# H16R6.net
KiCad netlist of a schematic drawn in EAGLE
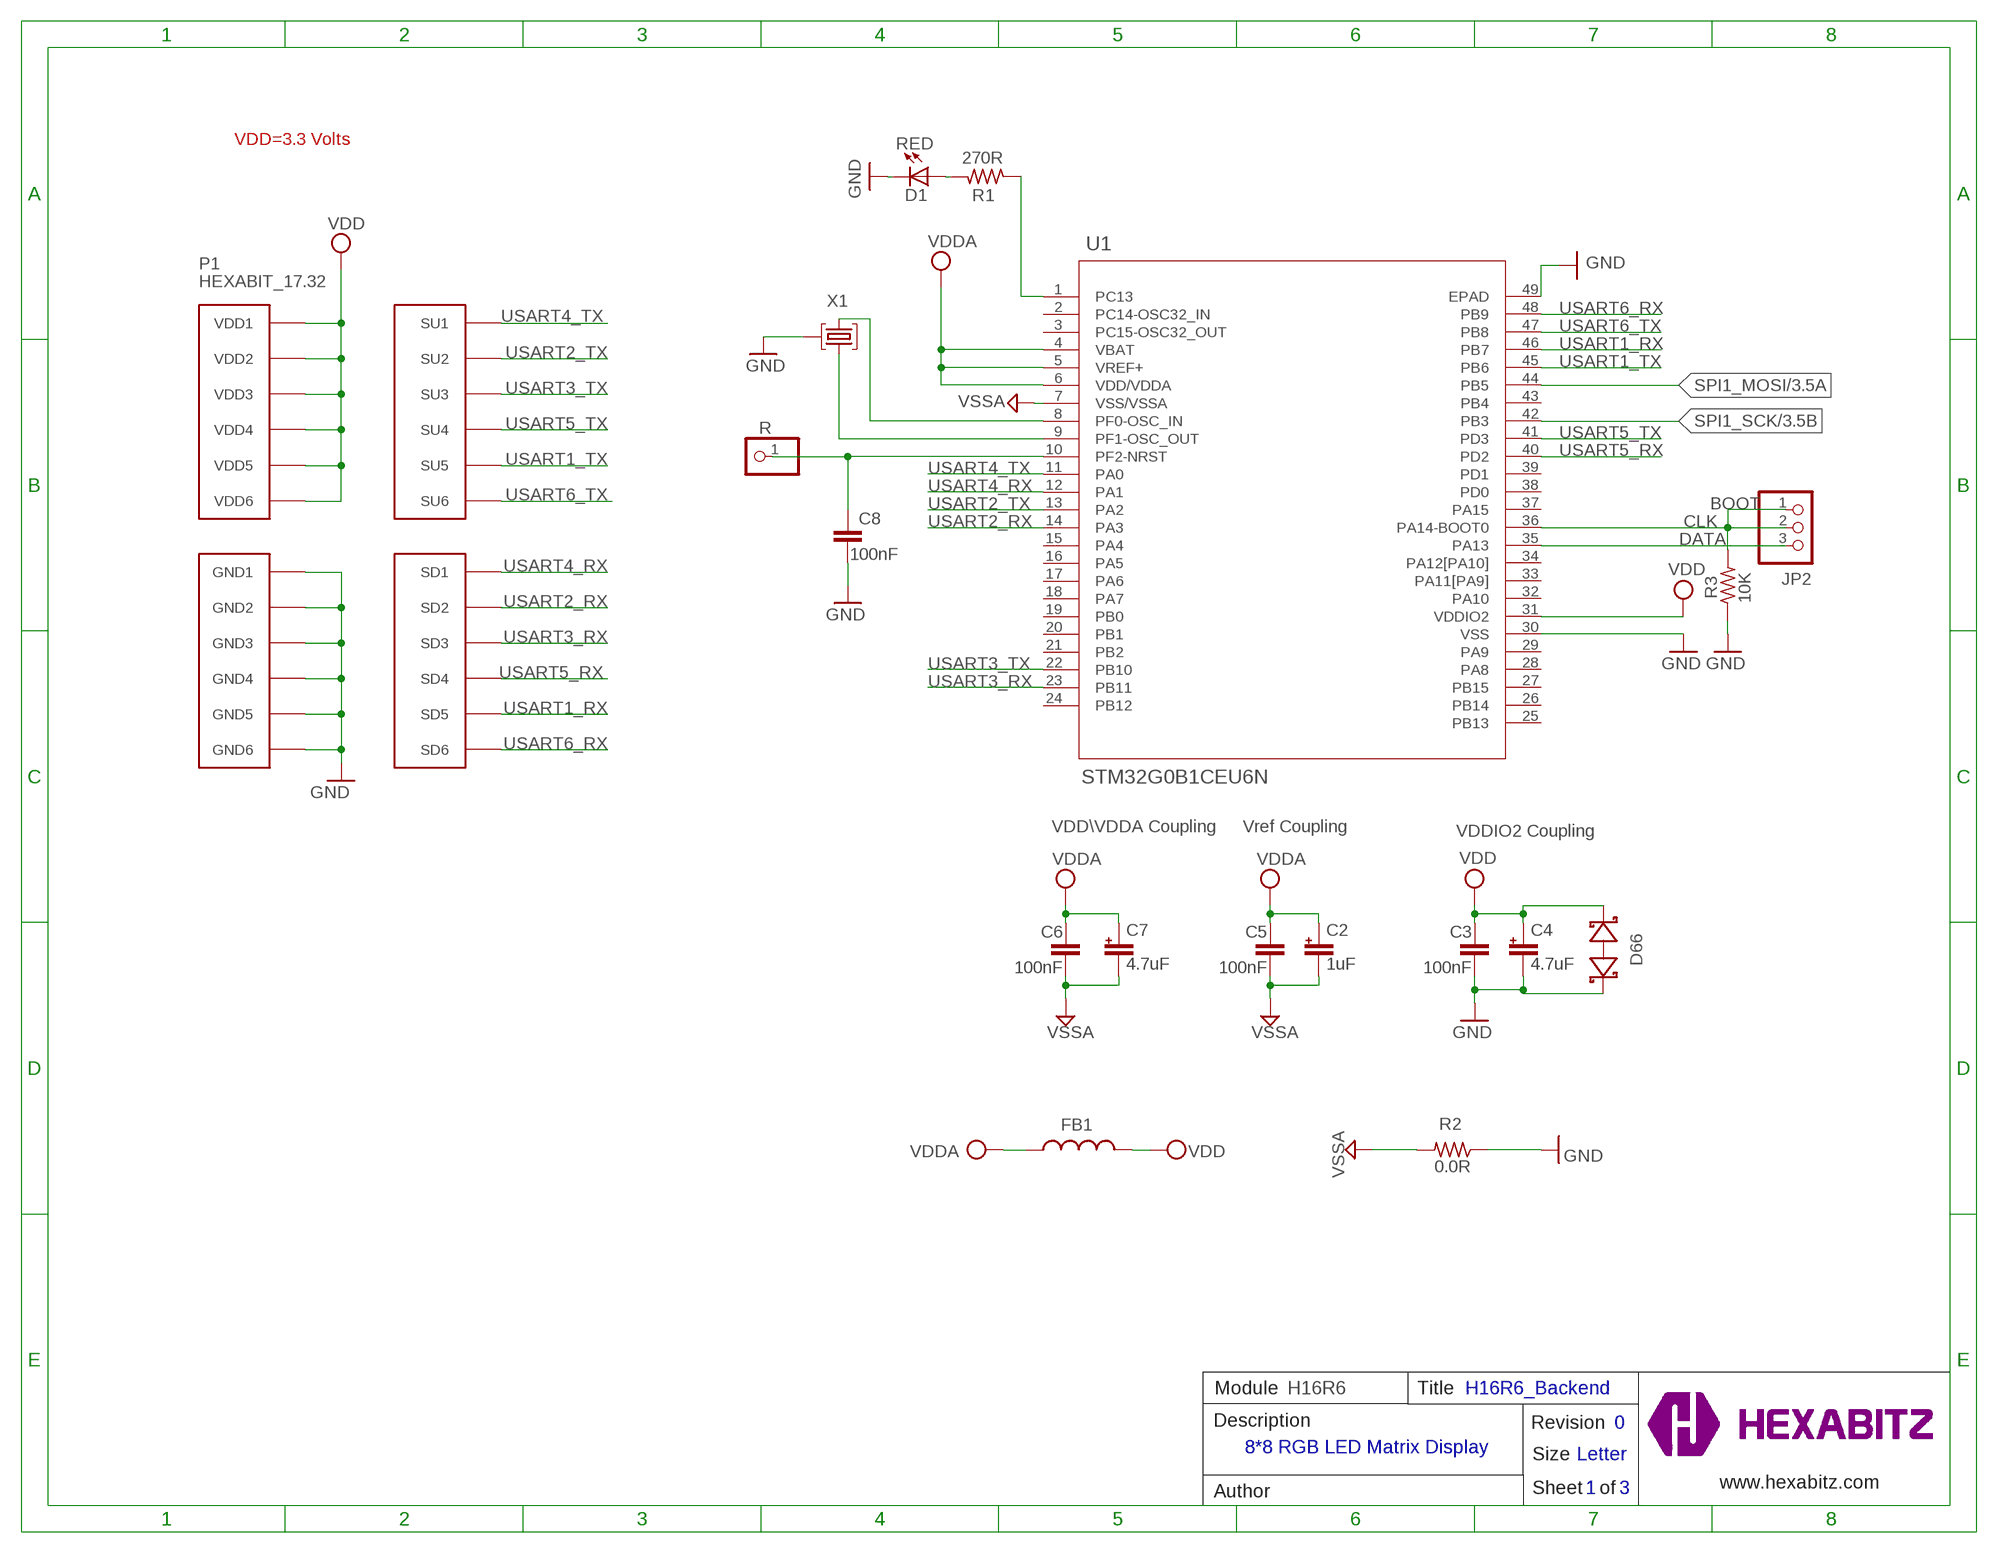
[diagram p0: schematic, sheet 1]
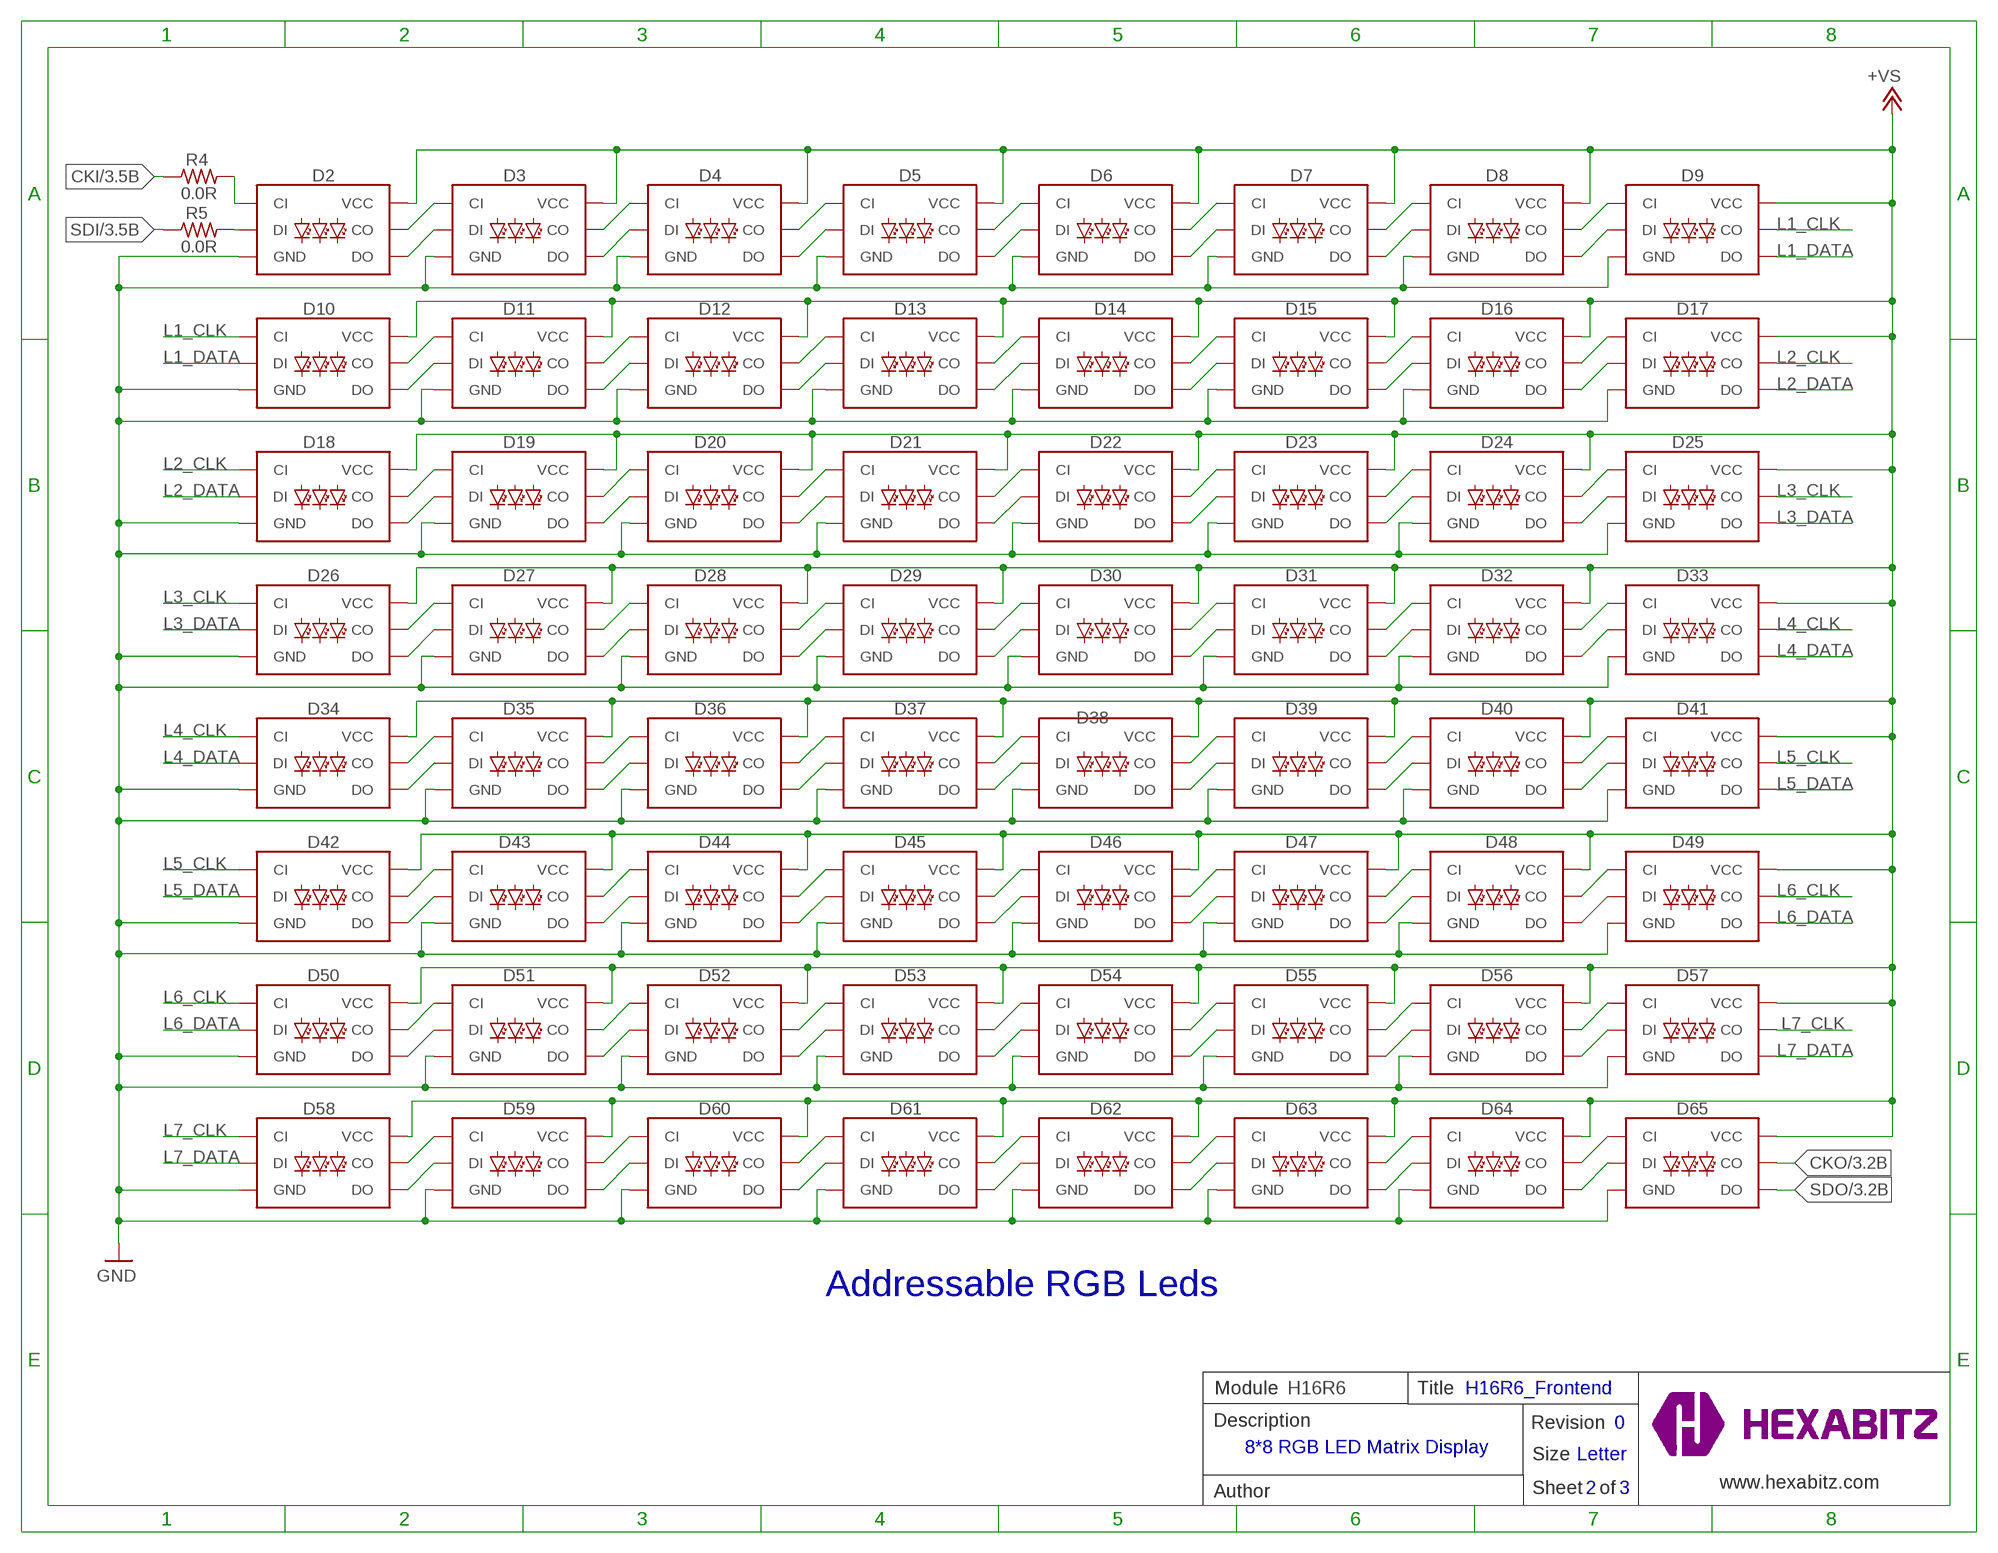
[diagram p1: schematic, sheet 2]
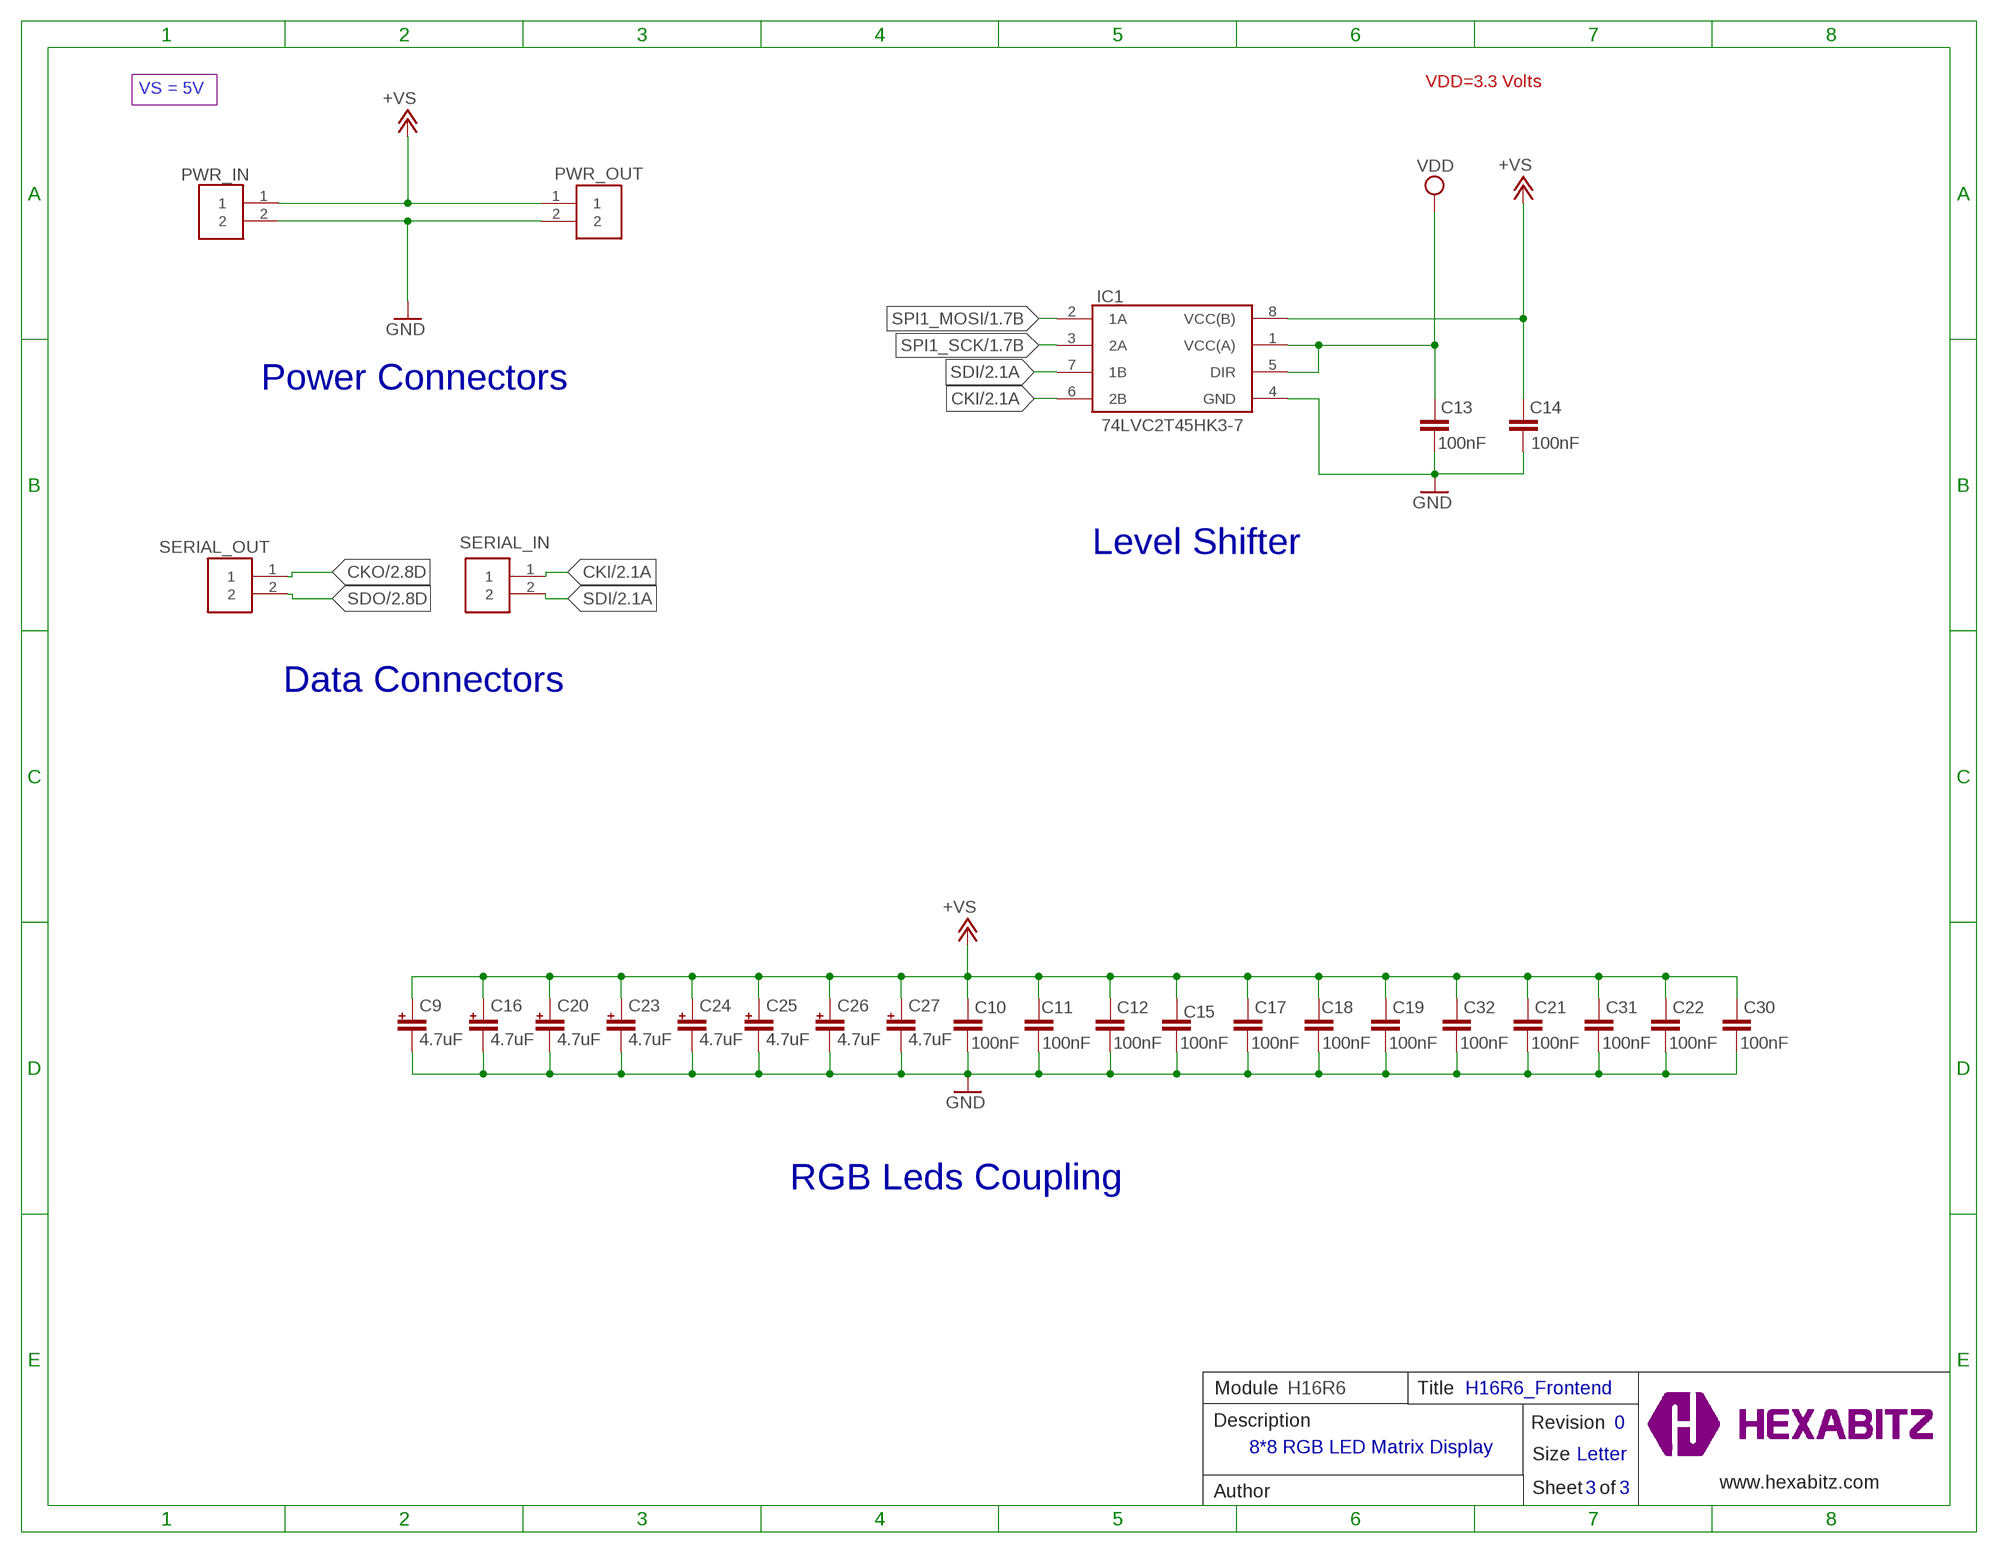
[diagram p2: schematic, sheet 3]

(export (version "E")
  (design (tool "Eeschema 10.0.6"))
  (components
    (comp (ref "C2")
      (value "1uF")
      (footprint "eagle-import:C-0402-POL")
      (libsource (lib "eagle-import") (part "C-0402-POL"))
    )
    (comp (ref "C3")
      (value "100nF")
      (footprint "eagle-import:C-0402")
      (libsource (lib "eagle-import") (part "C-0402"))
    )
    (comp (ref "C4")
      (value "4.7uF")
      (footprint "eagle-import:C-0402-POL")
      (libsource (lib "eagle-import") (part "C-0402-POL"))
    )
    (comp (ref "C5")
      (value "100nF")
      (footprint "eagle-import:C-0402")
      (libsource (lib "eagle-import") (part "C-0402"))
    )
    (comp (ref "C6")
      (value "100nF")
      (footprint "eagle-import:C-0402")
      (libsource (lib "eagle-import") (part "C-0402"))
    )
    (comp (ref "C7")
      (value "4.7uF")
      (footprint "eagle-import:C-0402-POL")
      (libsource (lib "eagle-import") (part "C-0402-POL"))
    )
    (comp (ref "C8")
      (value "100nF")
      (footprint "eagle-import:C-0402")
      (libsource (lib "eagle-import") (part "C-0402"))
    )
    (comp (ref "D1")
      (value "RED")
      (footprint "eagle-import:VLMS1300-GS08")
      (fields
        (field (name "MPN") "VLMS1300-GS08")
        (field (name "MFN") "Vishay")
        (field (name "MPN_1") "VLMS1300-GS08")
        (field (name "OCTOPART_URL") "https://octopart.com/vlms1300-gs08-vishay-21709201?r=sp&s=_gcP4_q8T1SC6PJQPTQ9yA")
      )
      (libsource (lib "eagle-import") (part "VLMS1300-GS08"))
    )
    (comp (ref "D66")
      (value "BOURNS_CDSOD323-T03SCBOURNS_CDSOD323-T03SC_0_0")
      (footprint "eagle-import:BOURNS_CDSOD323-T03SC_0")
      (fields (field (name "MPN") "CDSOD323-T03SC"))
      (libsource (lib "eagle-import") (part "BOURNS_CDSOD323-T03SCBOURNS_CDSOD323-T03SC_0_0"))
    )
    (comp (ref "FB1")
      (value "FB-TDK_MMZ1608Y300B")
      (footprint "eagle-import:FB-TDK_MMZ1608Y300B")
      (fields
        (field (name "MFN") "TDK ")
        (field (name "MPN") "MMZ1608Y300B")
        (field (name "OCTOPART_URL") "https://octopart.com/mmz1608y300b-tdk-368280?r=sp&s=cd9_2ZEqQ9q9UNBuQgHAiA")
      )
      (libsource (lib "eagle-import") (part "FB-TDK_MMZ1608Y300B"))
    )
    (comp (ref "JP2")
      (value "PINHD-1X3")
      (footprint "eagle-import:1X03")
      (libsource (lib "eagle-import") (part "PINHD-1X3"))
    )
    (comp (ref "P1")
      (value "HEXABIT_17.32")
      (footprint "eagle-import:HEXABIT_17.32")
      (libsource (lib "eagle-import") (part "HEXABIT_?17.32"))
    )
    (comp (ref "R")
      (value "R")
      (footprint "eagle-import:1X01")
      (fields (field (name "MPN") "87227-1"))
      (libsource (lib "eagle-import") (part "PINHD-1X1"))
    )
    (comp (ref "R1")
      (value "270R")
      (footprint "eagle-import:R-0402")
      (libsource (lib "eagle-import") (part "R-0402"))
    )
    (comp (ref "R2")
      (value "0.0R")
      (footprint "eagle-import:R-0402")
      (fields
        (field (name "MFN") "Yageo")
        (field (name "MPN") "RC0603JR-070RL")
        (field (name "OCTOPART_URL") "https://octopart.com/rc0603jr-070rl-yageo-1241539?r=sp&s=X2NteqRjRNWrnx42Y0aliA")
        (field (name "RESISTANCE") "0.0 Ohm")
      )
      (libsource (lib "eagle-import") (part "R-0402"))
    )
    (comp (ref "R3")
      (value "10K")
      (footprint "eagle-import:R-0402")
      (libsource (lib "eagle-import") (part "R-0402"))
    )
    (comp (ref "TRIMBLE-LOGO1")
      (value "HEXA-LOGO")
      (footprint "eagle-import:HEXA-LOGO")
      (libsource (lib "eagle-import") (part "HEXA-LOGO"))
    )
    (comp (ref "U1")
      (value "STM32G0B1CEU6N")
      (footprint "eagle-import:HEXABITZ_ICS_QFN_B1CEU6_STM-L")
      (libsource (lib "eagle-import") (part "STM32G0B1CEU6N"))
    )
    (comp (ref "X1")
      (value "XTALL_CSTCE8M00G52")
      (footprint "eagle-import:XTALL_CSTCE8M00G52")
      (fields (field (name "MPN") "CSTCE8M00G52Z-R0"))
      (libsource (lib "eagle-import") (part "XTALL_CSTCE8M00G52"))
    )
    (comp (ref "C9")
      (value "4.7uF")
      (footprint "eagle-import:C-0402-POL")
      (libsource (lib "eagle-import") (part "C-0402-POL"))
    )
    (comp (ref "C10")
      (value "100nF")
      (footprint "eagle-import:C-0402")
      (libsource (lib "eagle-import") (part "C-0402"))
    )
    (comp (ref "C11")
      (value "100nF")
      (footprint "eagle-import:C-0402")
      (libsource (lib "eagle-import") (part "C-0402"))
    )
    (comp (ref "C12")
      (value "100nF")
      (footprint "eagle-import:C-0402")
      (libsource (lib "eagle-import") (part "C-0402"))
    )
    (comp (ref "C13")
      (value "100nF")
      (footprint "eagle-import:C-0402")
      (libsource (lib "eagle-import") (part "C-0402"))
    )
    (comp (ref "C14")
      (value "100nF")
      (footprint "eagle-import:C-0402")
      (libsource (lib "eagle-import") (part "C-0402"))
    )
    (comp (ref "C15")
      (value "100nF")
      (footprint "eagle-import:C-0402")
      (libsource (lib "eagle-import") (part "C-0402"))
    )
    (comp (ref "C16")
      (value "4.7uF")
      (footprint "eagle-import:C-0402-POL")
      (libsource (lib "eagle-import") (part "C-0402-POL"))
    )
    (comp (ref "C17")
      (value "100nF")
      (footprint "eagle-import:C-0402")
      (libsource (lib "eagle-import") (part "C-0402"))
    )
    (comp (ref "C18")
      (value "100nF")
      (footprint "eagle-import:C-0402")
      (libsource (lib "eagle-import") (part "C-0402"))
    )
    (comp (ref "C19")
      (value "100nF")
      (footprint "eagle-import:C-0402")
      (libsource (lib "eagle-import") (part "C-0402"))
    )
    (comp (ref "C20")
      (value "4.7uF")
      (footprint "eagle-import:C-0402-POL")
      (libsource (lib "eagle-import") (part "C-0402-POL"))
    )
    (comp (ref "C21")
      (value "100nF")
      (footprint "eagle-import:C-0402")
      (libsource (lib "eagle-import") (part "C-0402"))
    )
    (comp (ref "C22")
      (value "100nF")
      (footprint "eagle-import:C-0402")
      (libsource (lib "eagle-import") (part "C-0402"))
    )
    (comp (ref "C23")
      (value "4.7uF")
      (footprint "eagle-import:C-0402-POL")
      (libsource (lib "eagle-import") (part "C-0402-POL"))
    )
    (comp (ref "C24")
      (value "4.7uF")
      (footprint "eagle-import:C-0402-POL")
      (libsource (lib "eagle-import") (part "C-0402-POL"))
    )
    (comp (ref "C25")
      (value "4.7uF")
      (footprint "eagle-import:C-0402-POL")
      (libsource (lib "eagle-import") (part "C-0402-POL"))
    )
    (comp (ref "C26")
      (value "4.7uF")
      (footprint "eagle-import:C-0402-POL")
      (libsource (lib "eagle-import") (part "C-0402-POL"))
    )
    (comp (ref "C27")
      (value "4.7uF")
      (footprint "eagle-import:C-0402-POL")
      (libsource (lib "eagle-import") (part "C-0402-POL"))
    )
    (comp (ref "C30")
      (value "100nF")
      (footprint "eagle-import:C-0402")
      (libsource (lib "eagle-import") (part "C-0402"))
    )
    (comp (ref "C31")
      (value "100nF")
      (footprint "eagle-import:C-0402")
      (libsource (lib "eagle-import") (part "C-0402"))
    )
    (comp (ref "C32")
      (value "100nF")
      (footprint "eagle-import:C-0402")
      (libsource (lib "eagle-import") (part "C-0402"))
    )
    (comp (ref "IC1")
      (value "74LVC2T45HK3-7")
      (footprint "eagle-import:74LVC2T45HK37")
      (fields (field (name "MOUSER_PART_NUMBER") "621-74LVC2T45HK3-7"))
      (libsource (lib "eagle-import") (part "74LVC2T45HK3-7"))
    )
    (comp (ref "PWR_IN")
      (value "3-644456-2")
      (footprint "eagle-import:TE_3-644456-2")
      (fields (field (name "MF") "TE Connectivity") (field (name "MPN") "87224-1"))
      (libsource (lib "eagle-import") (part "3-644456-2"))
    )
    (comp (ref "PWR_OUT")
      (value "3-644456-2")
      (footprint "eagle-import:TE_3-644456-2")
      (fields (field (name "MF") "TE Connectivity") (field (name "MPN") "87224-1"))
      (libsource (lib "eagle-import") (part "3-644456-2"))
    )
    (comp (ref "SERIAL_IN")
      (value "3-644456-2")
      (footprint "eagle-import:TE_3-644456-2")
      (fields (field (name "MF") "TE Connectivity") (field (name "MPN") "87224-1"))
      (libsource (lib "eagle-import") (part "3-644456-2"))
    )
    (comp (ref "SERIAL_OUT")
      (value "3-644456-2")
      (footprint "eagle-import:TE_3-644456-2")
      (fields (field (name "MF") "TE Connectivity") (field (name "MPN") "87224-1"))
      (libsource (lib "eagle-import") (part "3-644456-2"))
    )
    (comp (ref "D2")
      (value "SPARKFUN-LED_APA102-2020")
      (footprint "eagle-import:SPARKFUN-LED_APA102-2020")
      (libsource (lib "eagle-import") (part "SPARKFUN-LED_APA102-2020"))
    )
    (comp (ref "D3")
      (value "SPARKFUN-LED_APA102-2020")
      (footprint "eagle-import:SPARKFUN-LED_APA102-2020")
      (libsource (lib "eagle-import") (part "SPARKFUN-LED_APA102-2020"))
    )
    (comp (ref "D4")
      (value "SPARKFUN-LED_APA102-2020")
      (footprint "eagle-import:SPARKFUN-LED_APA102-2020")
      (libsource (lib "eagle-import") (part "SPARKFUN-LED_APA102-2020"))
    )
    (comp (ref "D5")
      (value "SPARKFUN-LED_APA102-2020")
      (footprint "eagle-import:SPARKFUN-LED_APA102-2020")
      (libsource (lib "eagle-import") (part "SPARKFUN-LED_APA102-2020"))
    )
    (comp (ref "D6")
      (value "SPARKFUN-LED_APA102-2020")
      (footprint "eagle-import:SPARKFUN-LED_APA102-2020")
      (libsource (lib "eagle-import") (part "SPARKFUN-LED_APA102-2020"))
    )
    (comp (ref "D7")
      (value "SPARKFUN-LED_APA102-2020")
      (footprint "eagle-import:SPARKFUN-LED_APA102-2020")
      (libsource (lib "eagle-import") (part "SPARKFUN-LED_APA102-2020"))
    )
    (comp (ref "D8")
      (value "SPARKFUN-LED_APA102-2020")
      (footprint "eagle-import:SPARKFUN-LED_APA102-2020")
      (libsource (lib "eagle-import") (part "SPARKFUN-LED_APA102-2020"))
    )
    (comp (ref "D9")
      (value "SPARKFUN-LED_APA102-2020")
      (footprint "eagle-import:SPARKFUN-LED_APA102-2020")
      (libsource (lib "eagle-import") (part "SPARKFUN-LED_APA102-2020"))
    )
    (comp (ref "D10")
      (value "SPARKFUN-LED_APA102-2020")
      (footprint "eagle-import:SPARKFUN-LED_APA102-2020")
      (libsource (lib "eagle-import") (part "SPARKFUN-LED_APA102-2020"))
    )
    (comp (ref "D11")
      (value "SPARKFUN-LED_APA102-2020")
      (footprint "eagle-import:SPARKFUN-LED_APA102-2020")
      (libsource (lib "eagle-import") (part "SPARKFUN-LED_APA102-2020"))
    )
    (comp (ref "D12")
      (value "SPARKFUN-LED_APA102-2020")
      (footprint "eagle-import:SPARKFUN-LED_APA102-2020")
      (libsource (lib "eagle-import") (part "SPARKFUN-LED_APA102-2020"))
    )
    (comp (ref "D13")
      (value "SPARKFUN-LED_APA102-2020")
      (footprint "eagle-import:SPARKFUN-LED_APA102-2020")
      (libsource (lib "eagle-import") (part "SPARKFUN-LED_APA102-2020"))
    )
    (comp (ref "D14")
      (value "SPARKFUN-LED_APA102-2020")
      (footprint "eagle-import:SPARKFUN-LED_APA102-2020")
      (libsource (lib "eagle-import") (part "SPARKFUN-LED_APA102-2020"))
    )
    (comp (ref "D15")
      (value "SPARKFUN-LED_APA102-2020")
      (footprint "eagle-import:SPARKFUN-LED_APA102-2020")
      (libsource (lib "eagle-import") (part "SPARKFUN-LED_APA102-2020"))
    )
    (comp (ref "D16")
      (value "SPARKFUN-LED_APA102-2020")
      (footprint "eagle-import:SPARKFUN-LED_APA102-2020")
      (libsource (lib "eagle-import") (part "SPARKFUN-LED_APA102-2020"))
    )
    (comp (ref "D17")
      (value "SPARKFUN-LED_APA102-2020")
      (footprint "eagle-import:SPARKFUN-LED_APA102-2020")
      (libsource (lib "eagle-import") (part "SPARKFUN-LED_APA102-2020"))
    )
    (comp (ref "D18")
      (value "SPARKFUN-LED_APA102-2020")
      (footprint "eagle-import:SPARKFUN-LED_APA102-2020")
      (libsource (lib "eagle-import") (part "SPARKFUN-LED_APA102-2020"))
    )
    (comp (ref "D19")
      (value "SPARKFUN-LED_APA102-2020")
      (footprint "eagle-import:SPARKFUN-LED_APA102-2020")
      (libsource (lib "eagle-import") (part "SPARKFUN-LED_APA102-2020"))
    )
    (comp (ref "D20")
      (value "SPARKFUN-LED_APA102-2020")
      (footprint "eagle-import:SPARKFUN-LED_APA102-2020")
      (libsource (lib "eagle-import") (part "SPARKFUN-LED_APA102-2020"))
    )
    (comp (ref "D21")
      (value "SPARKFUN-LED_APA102-2020")
      (footprint "eagle-import:SPARKFUN-LED_APA102-2020")
      (libsource (lib "eagle-import") (part "SPARKFUN-LED_APA102-2020"))
    )
    (comp (ref "D22")
      (value "SPARKFUN-LED_APA102-2020")
      (footprint "eagle-import:SPARKFUN-LED_APA102-2020")
      (libsource (lib "eagle-import") (part "SPARKFUN-LED_APA102-2020"))
    )
    (comp (ref "D23")
      (value "SPARKFUN-LED_APA102-2020")
      (footprint "eagle-import:SPARKFUN-LED_APA102-2020")
      (libsource (lib "eagle-import") (part "SPARKFUN-LED_APA102-2020"))
    )
    (comp (ref "D24")
      (value "SPARKFUN-LED_APA102-2020")
      (footprint "eagle-import:SPARKFUN-LED_APA102-2020")
      (libsource (lib "eagle-import") (part "SPARKFUN-LED_APA102-2020"))
    )
    (comp (ref "D25")
      (value "SPARKFUN-LED_APA102-2020")
      (footprint "eagle-import:SPARKFUN-LED_APA102-2020")
      (libsource (lib "eagle-import") (part "SPARKFUN-LED_APA102-2020"))
    )
    (comp (ref "D26")
      (value "SPARKFUN-LED_APA102-2020")
      (footprint "eagle-import:SPARKFUN-LED_APA102-2020")
      (libsource (lib "eagle-import") (part "SPARKFUN-LED_APA102-2020"))
    )
    (comp (ref "D27")
      (value "SPARKFUN-LED_APA102-2020")
      (footprint "eagle-import:SPARKFUN-LED_APA102-2020")
      (libsource (lib "eagle-import") (part "SPARKFUN-LED_APA102-2020"))
    )
    (comp (ref "D28")
      (value "SPARKFUN-LED_APA102-2020")
      (footprint "eagle-import:SPARKFUN-LED_APA102-2020")
      (libsource (lib "eagle-import") (part "SPARKFUN-LED_APA102-2020"))
    )
    (comp (ref "D29")
      (value "SPARKFUN-LED_APA102-2020")
      (footprint "eagle-import:SPARKFUN-LED_APA102-2020")
      (libsource (lib "eagle-import") (part "SPARKFUN-LED_APA102-2020"))
    )
    (comp (ref "D30")
      (value "SPARKFUN-LED_APA102-2020")
      (footprint "eagle-import:SPARKFUN-LED_APA102-2020")
      (libsource (lib "eagle-import") (part "SPARKFUN-LED_APA102-2020"))
    )
    (comp (ref "D31")
      (value "SPARKFUN-LED_APA102-2020")
      (footprint "eagle-import:SPARKFUN-LED_APA102-2020")
      (libsource (lib "eagle-import") (part "SPARKFUN-LED_APA102-2020"))
    )
    (comp (ref "D32")
      (value "SPARKFUN-LED_APA102-2020")
      (footprint "eagle-import:SPARKFUN-LED_APA102-2020")
      (libsource (lib "eagle-import") (part "SPARKFUN-LED_APA102-2020"))
    )
    (comp (ref "D33")
      (value "SPARKFUN-LED_APA102-2020")
      (footprint "eagle-import:SPARKFUN-LED_APA102-2020")
      (libsource (lib "eagle-import") (part "SPARKFUN-LED_APA102-2020"))
    )
    (comp (ref "D34")
      (value "SPARKFUN-LED_APA102-2020")
      (footprint "eagle-import:SPARKFUN-LED_APA102-2020")
      (libsource (lib "eagle-import") (part "SPARKFUN-LED_APA102-2020"))
    )
    (comp (ref "D35")
      (value "SPARKFUN-LED_APA102-2020")
      (footprint "eagle-import:SPARKFUN-LED_APA102-2020")
      (libsource (lib "eagle-import") (part "SPARKFUN-LED_APA102-2020"))
    )
    (comp (ref "D36")
      (value "SPARKFUN-LED_APA102-2020")
      (footprint "eagle-import:SPARKFUN-LED_APA102-2020")
      (libsource (lib "eagle-import") (part "SPARKFUN-LED_APA102-2020"))
    )
    (comp (ref "D37")
      (value "SPARKFUN-LED_APA102-2020")
      (footprint "eagle-import:SPARKFUN-LED_APA102-2020")
      (libsource (lib "eagle-import") (part "SPARKFUN-LED_APA102-2020"))
    )
    (comp (ref "D38")
      (value "SPARKFUN-LED_APA102-2020")
      (footprint "eagle-import:SPARKFUN-LED_APA102-2020")
      (libsource (lib "eagle-import") (part "SPARKFUN-LED_APA102-2020"))
    )
    (comp (ref "D39")
      (value "SPARKFUN-LED_APA102-2020")
      (footprint "eagle-import:SPARKFUN-LED_APA102-2020")
      (libsource (lib "eagle-import") (part "SPARKFUN-LED_APA102-2020"))
    )
    (comp (ref "D40")
      (value "SPARKFUN-LED_APA102-2020")
      (footprint "eagle-import:SPARKFUN-LED_APA102-2020")
      (libsource (lib "eagle-import") (part "SPARKFUN-LED_APA102-2020"))
    )
    (comp (ref "D41")
      (value "SPARKFUN-LED_APA102-2020")
      (footprint "eagle-import:SPARKFUN-LED_APA102-2020")
      (libsource (lib "eagle-import") (part "SPARKFUN-LED_APA102-2020"))
    )
    (comp (ref "D42")
      (value "SPARKFUN-LED_APA102-2020")
      (footprint "eagle-import:SPARKFUN-LED_APA102-2020")
      (libsource (lib "eagle-import") (part "SPARKFUN-LED_APA102-2020"))
    )
    (comp (ref "D43")
      (value "SPARKFUN-LED_APA102-2020")
      (footprint "eagle-import:SPARKFUN-LED_APA102-2020")
      (libsource (lib "eagle-import") (part "SPARKFUN-LED_APA102-2020"))
    )
    (comp (ref "D44")
      (value "SPARKFUN-LED_APA102-2020")
      (footprint "eagle-import:SPARKFUN-LED_APA102-2020")
      (libsource (lib "eagle-import") (part "SPARKFUN-LED_APA102-2020"))
    )
    (comp (ref "D45")
      (value "SPARKFUN-LED_APA102-2020")
      (footprint "eagle-import:SPARKFUN-LED_APA102-2020")
      (libsource (lib "eagle-import") (part "SPARKFUN-LED_APA102-2020"))
    )
    (comp (ref "D46")
      (value "SPARKFUN-LED_APA102-2020")
      (footprint "eagle-import:SPARKFUN-LED_APA102-2020")
      (libsource (lib "eagle-import") (part "SPARKFUN-LED_APA102-2020"))
    )
    (comp (ref "D47")
      (value "SPARKFUN-LED_APA102-2020")
      (footprint "eagle-import:SPARKFUN-LED_APA102-2020")
      (libsource (lib "eagle-import") (part "SPARKFUN-LED_APA102-2020"))
    )
    (comp (ref "D48")
      (value "SPARKFUN-LED_APA102-2020")
      (footprint "eagle-import:SPARKFUN-LED_APA102-2020")
      (libsource (lib "eagle-import") (part "SPARKFUN-LED_APA102-2020"))
    )
    (comp (ref "D49")
      (value "SPARKFUN-LED_APA102-2020")
      (footprint "eagle-import:SPARKFUN-LED_APA102-2020")
      (libsource (lib "eagle-import") (part "SPARKFUN-LED_APA102-2020"))
    )
    (comp (ref "D50")
      (value "SPARKFUN-LED_APA102-2020")
      (footprint "eagle-import:SPARKFUN-LED_APA102-2020")
      (libsource (lib "eagle-import") (part "SPARKFUN-LED_APA102-2020"))
    )
    (comp (ref "D51")
      (value "SPARKFUN-LED_APA102-2020")
      (footprint "eagle-import:SPARKFUN-LED_APA102-2020")
      (libsource (lib "eagle-import") (part "SPARKFUN-LED_APA102-2020"))
    )
    (comp (ref "D52")
      (value "SPARKFUN-LED_APA102-2020")
      (footprint "eagle-import:SPARKFUN-LED_APA102-2020")
      (libsource (lib "eagle-import") (part "SPARKFUN-LED_APA102-2020"))
    )
    (comp (ref "D53")
      (value "SPARKFUN-LED_APA102-2020")
      (footprint "eagle-import:SPARKFUN-LED_APA102-2020")
      (libsource (lib "eagle-import") (part "SPARKFUN-LED_APA102-2020"))
    )
    (comp (ref "D54")
      (value "SPARKFUN-LED_APA102-2020")
      (footprint "eagle-import:SPARKFUN-LED_APA102-2020")
      (libsource (lib "eagle-import") (part "SPARKFUN-LED_APA102-2020"))
    )
    (comp (ref "D55")
      (value "SPARKFUN-LED_APA102-2020")
      (footprint "eagle-import:SPARKFUN-LED_APA102-2020")
      (libsource (lib "eagle-import") (part "SPARKFUN-LED_APA102-2020"))
    )
    (comp (ref "D56")
      (value "SPARKFUN-LED_APA102-2020")
      (footprint "eagle-import:SPARKFUN-LED_APA102-2020")
      (libsource (lib "eagle-import") (part "SPARKFUN-LED_APA102-2020"))
    )
    (comp (ref "D57")
      (value "SPARKFUN-LED_APA102-2020")
      (footprint "eagle-import:SPARKFUN-LED_APA102-2020")
      (libsource (lib "eagle-import") (part "SPARKFUN-LED_APA102-2020"))
    )
    (comp (ref "D58")
      (value "SPARKFUN-LED_APA102-2020")
      (footprint "eagle-import:SPARKFUN-LED_APA102-2020")
      (libsource (lib "eagle-import") (part "SPARKFUN-LED_APA102-2020"))
    )
    (comp (ref "D59")
      (value "SPARKFUN-LED_APA102-2020")
      (footprint "eagle-import:SPARKFUN-LED_APA102-2020")
      (libsource (lib "eagle-import") (part "SPARKFUN-LED_APA102-2020"))
    )
    (comp (ref "D60")
      (value "SPARKFUN-LED_APA102-2020")
      (footprint "eagle-import:SPARKFUN-LED_APA102-2020")
      (libsource (lib "eagle-import") (part "SPARKFUN-LED_APA102-2020"))
    )
    (comp (ref "D61")
      (value "SPARKFUN-LED_APA102-2020")
      (footprint "eagle-import:SPARKFUN-LED_APA102-2020")
      (libsource (lib "eagle-import") (part "SPARKFUN-LED_APA102-2020"))
    )
    (comp (ref "D62")
      (value "SPARKFUN-LED_APA102-2020")
      (footprint "eagle-import:SPARKFUN-LED_APA102-2020")
      (libsource (lib "eagle-import") (part "SPARKFUN-LED_APA102-2020"))
    )
    (comp (ref "D63")
      (value "SPARKFUN-LED_APA102-2020")
      (footprint "eagle-import:SPARKFUN-LED_APA102-2020")
      (libsource (lib "eagle-import") (part "SPARKFUN-LED_APA102-2020"))
    )
    (comp (ref "D64")
      (value "SPARKFUN-LED_APA102-2020")
      (footprint "eagle-import:SPARKFUN-LED_APA102-2020")
      (libsource (lib "eagle-import") (part "SPARKFUN-LED_APA102-2020"))
    )
    (comp (ref "D65")
      (value "SPARKFUN-LED_APA102-2020")
      (footprint "eagle-import:SPARKFUN-LED_APA102-2020")
      (libsource (lib "eagle-import") (part "SPARKFUN-LED_APA102-2020"))
    )
    (comp (ref "R4")
      (value "0.0R")
      (footprint "eagle-import:R-0402")
      (libsource (lib "eagle-import") (part "R-0402"))
    )
    (comp (ref "R5")
      (value "0.0R")
      (footprint "eagle-import:R-0402")
      (libsource (lib "eagle-import") (part "R-0402"))
    )
  )
  (nets
    (net (code "1") (name "+VS") (class "Default")
      (node (ref "C10") (pin "1") (pinfunction "1_1") (pintype "passive"))
      (node (ref "C11") (pin "1") (pinfunction "1_1") (pintype "passive"))
      (node (ref "C12") (pin "1") (pinfunction "1_1") (pintype "passive"))
      (node (ref "C14") (pin "1") (pinfunction "1_1") (pintype "passive"))
      (node (ref "C15") (pin "1") (pinfunction "1_1") (pintype "passive"))
      (node (ref "C16") (pin "1") (pinfunction "1_1") (pintype "passive"))
      (node (ref "C17") (pin "1") (pinfunction "1_1") (pintype "passive"))
      (node (ref "C18") (pin "1") (pinfunction "1_1") (pintype "passive"))
      (node (ref "C19") (pin "1") (pinfunction "1_1") (pintype "passive"))
      (node (ref "C20") (pin "1") (pinfunction "1_1") (pintype "passive"))
      (node (ref "C21") (pin "1") (pinfunction "1_1") (pintype "passive"))
      (node (ref "C22") (pin "1") (pinfunction "1_1") (pintype "passive"))
      (node (ref "C23") (pin "1") (pinfunction "1_1") (pintype "passive"))
      (node (ref "C24") (pin "1") (pinfunction "1_1") (pintype "passive"))
      (node (ref "C25") (pin "1") (pinfunction "1_1") (pintype "passive"))
      (node (ref "C26") (pin "1") (pinfunction "1_1") (pintype "passive"))
      (node (ref "C27") (pin "1") (pinfunction "1_1") (pintype "passive"))
      (node (ref "C30") (pin "1") (pinfunction "1_1") (pintype "passive"))
      (node (ref "C31") (pin "1") (pinfunction "1_1") (pintype "passive"))
      (node (ref "C32") (pin "1") (pinfunction "1_1") (pintype "passive"))
      (node (ref "C9") (pin "1") (pinfunction "1_1") (pintype "passive"))
      (node (ref "D10") (pin "VDD") (pinfunction "VCC_VDD") (pintype "bidirectional"))
      (node (ref "D10") (pin "VDD1") (pinfunction "VCC_VDD1") (pintype "bidirectional"))
      (node (ref "D11") (pin "VDD") (pinfunction "VCC_VDD") (pintype "bidirectional"))
      (node (ref "D11") (pin "VDD1") (pinfunction "VCC_VDD1") (pintype "bidirectional"))
      (node (ref "D12") (pin "VDD") (pinfunction "VCC_VDD") (pintype "bidirectional"))
      (node (ref "D12") (pin "VDD1") (pinfunction "VCC_VDD1") (pintype "bidirectional"))
      (node (ref "D13") (pin "VDD") (pinfunction "VCC_VDD") (pintype "bidirectional"))
      (node (ref "D13") (pin "VDD1") (pinfunction "VCC_VDD1") (pintype "bidirectional"))
      (node (ref "D14") (pin "VDD") (pinfunction "VCC_VDD") (pintype "bidirectional"))
      (node (ref "D14") (pin "VDD1") (pinfunction "VCC_VDD1") (pintype "bidirectional"))
      (node (ref "D15") (pin "VDD") (pinfunction "VCC_VDD") (pintype "bidirectional"))
      (node (ref "D15") (pin "VDD1") (pinfunction "VCC_VDD1") (pintype "bidirectional"))
      (node (ref "D16") (pin "VDD") (pinfunction "VCC_VDD") (pintype "bidirectional"))
      (node (ref "D16") (pin "VDD1") (pinfunction "VCC_VDD1") (pintype "bidirectional"))
      (node (ref "D17") (pin "VDD") (pinfunction "VCC_VDD") (pintype "bidirectional"))
      (node (ref "D17") (pin "VDD1") (pinfunction "VCC_VDD1") (pintype "bidirectional"))
      (node (ref "D18") (pin "VDD") (pinfunction "VCC_VDD") (pintype "bidirectional"))
      (node (ref "D18") (pin "VDD1") (pinfunction "VCC_VDD1") (pintype "bidirectional"))
      (node (ref "D19") (pin "VDD") (pinfunction "VCC_VDD") (pintype "bidirectional"))
      (node (ref "D19") (pin "VDD1") (pinfunction "VCC_VDD1") (pintype "bidirectional"))
      (node (ref "D2") (pin "VDD") (pinfunction "VCC_VDD") (pintype "bidirectional"))
      (node (ref "D2") (pin "VDD1") (pinfunction "VCC_VDD1") (pintype "bidirectional"))
      (node (ref "D20") (pin "VDD") (pinfunction "VCC_VDD") (pintype "bidirectional"))
      (node (ref "D20") (pin "VDD1") (pinfunction "VCC_VDD1") (pintype "bidirectional"))
      (node (ref "D21") (pin "VDD") (pinfunction "VCC_VDD") (pintype "bidirectional"))
      (node (ref "D21") (pin "VDD1") (pinfunction "VCC_VDD1") (pintype "bidirectional"))
      (node (ref "D22") (pin "VDD") (pinfunction "VCC_VDD") (pintype "bidirectional"))
      (node (ref "D22") (pin "VDD1") (pinfunction "VCC_VDD1") (pintype "bidirectional"))
      (node (ref "D23") (pin "VDD") (pinfunction "VCC_VDD") (pintype "bidirectional"))
      (node (ref "D23") (pin "VDD1") (pinfunction "VCC_VDD1") (pintype "bidirectional"))
      (node (ref "D24") (pin "VDD") (pinfunction "VCC_VDD") (pintype "bidirectional"))
      (node (ref "D24") (pin "VDD1") (pinfunction "VCC_VDD1") (pintype "bidirectional"))
      (node (ref "D25") (pin "VDD") (pinfunction "VCC_VDD") (pintype "bidirectional"))
      (node (ref "D25") (pin "VDD1") (pinfunction "VCC_VDD1") (pintype "bidirectional"))
      (node (ref "D26") (pin "VDD") (pinfunction "VCC_VDD") (pintype "bidirectional"))
      (node (ref "D26") (pin "VDD1") (pinfunction "VCC_VDD1") (pintype "bidirectional"))
      (node (ref "D27") (pin "VDD") (pinfunction "VCC_VDD") (pintype "bidirectional"))
      (node (ref "D27") (pin "VDD1") (pinfunction "VCC_VDD1") (pintype "bidirectional"))
      (node (ref "D28") (pin "VDD") (pinfunction "VCC_VDD") (pintype "bidirectional"))
      (node (ref "D28") (pin "VDD1") (pinfunction "VCC_VDD1") (pintype "bidirectional"))
      (node (ref "D29") (pin "VDD") (pinfunction "VCC_VDD") (pintype "bidirectional"))
      (node (ref "D29") (pin "VDD1") (pinfunction "VCC_VDD1") (pintype "bidirectional"))
      (node (ref "D3") (pin "VDD") (pinfunction "VCC_VDD") (pintype "bidirectional"))
      (node (ref "D3") (pin "VDD1") (pinfunction "VCC_VDD1") (pintype "bidirectional"))
      (node (ref "D30") (pin "VDD") (pinfunction "VCC_VDD") (pintype "bidirectional"))
      (node (ref "D30") (pin "VDD1") (pinfunction "VCC_VDD1") (pintype "bidirectional"))
      (node (ref "D31") (pin "VDD") (pinfunction "VCC_VDD") (pintype "bidirectional"))
      (node (ref "D31") (pin "VDD1") (pinfunction "VCC_VDD1") (pintype "bidirectional"))
      (node (ref "D32") (pin "VDD") (pinfunction "VCC_VDD") (pintype "bidirectional"))
      (node (ref "D32") (pin "VDD1") (pinfunction "VCC_VDD1") (pintype "bidirectional"))
      (node (ref "D33") (pin "VDD") (pinfunction "VCC_VDD") (pintype "bidirectional"))
      (node (ref "D33") (pin "VDD1") (pinfunction "VCC_VDD1") (pintype "bidirectional"))
      (node (ref "D34") (pin "VDD") (pinfunction "VCC_VDD") (pintype "bidirectional"))
      (node (ref "D34") (pin "VDD1") (pinfunction "VCC_VDD1") (pintype "bidirectional"))
      (node (ref "D35") (pin "VDD") (pinfunction "VCC_VDD") (pintype "bidirectional"))
      (node (ref "D35") (pin "VDD1") (pinfunction "VCC_VDD1") (pintype "bidirectional"))
      (node (ref "D36") (pin "VDD") (pinfunction "VCC_VDD") (pintype "bidirectional"))
      (node (ref "D36") (pin "VDD1") (pinfunction "VCC_VDD1") (pintype "bidirectional"))
      (node (ref "D37") (pin "VDD") (pinfunction "VCC_VDD") (pintype "bidirectional"))
      (node (ref "D37") (pin "VDD1") (pinfunction "VCC_VDD1") (pintype "bidirectional"))
      (node (ref "D38") (pin "VDD") (pinfunction "VCC_VDD") (pintype "bidirectional"))
      (node (ref "D38") (pin "VDD1") (pinfunction "VCC_VDD1") (pintype "bidirectional"))
      (node (ref "D39") (pin "VDD") (pinfunction "VCC_VDD") (pintype "bidirectional"))
      (node (ref "D39") (pin "VDD1") (pinfunction "VCC_VDD1") (pintype "bidirectional"))
      (node (ref "D4") (pin "VDD") (pinfunction "VCC_VDD") (pintype "bidirectional"))
      (node (ref "D4") (pin "VDD1") (pinfunction "VCC_VDD1") (pintype "bidirectional"))
      (node (ref "D40") (pin "VDD") (pinfunction "VCC_VDD") (pintype "bidirectional"))
      (node (ref "D40") (pin "VDD1") (pinfunction "VCC_VDD1") (pintype "bidirectional"))
      (node (ref "D41") (pin "VDD") (pinfunction "VCC_VDD") (pintype "bidirectional"))
      (node (ref "D41") (pin "VDD1") (pinfunction "VCC_VDD1") (pintype "bidirectional"))
      (node (ref "D42") (pin "VDD") (pinfunction "VCC_VDD") (pintype "bidirectional"))
      (node (ref "D42") (pin "VDD1") (pinfunction "VCC_VDD1") (pintype "bidirectional"))
      (node (ref "D43") (pin "VDD") (pinfunction "VCC_VDD") (pintype "bidirectional"))
      (node (ref "D43") (pin "VDD1") (pinfunction "VCC_VDD1") (pintype "bidirectional"))
      (node (ref "D44") (pin "VDD") (pinfunction "VCC_VDD") (pintype "bidirectional"))
      (node (ref "D44") (pin "VDD1") (pinfunction "VCC_VDD1") (pintype "bidirectional"))
      (node (ref "D45") (pin "VDD") (pinfunction "VCC_VDD") (pintype "bidirectional"))
      (node (ref "D45") (pin "VDD1") (pinfunction "VCC_VDD1") (pintype "bidirectional"))
      (node (ref "D46") (pin "VDD") (pinfunction "VCC_VDD") (pintype "bidirectional"))
      (node (ref "D46") (pin "VDD1") (pinfunction "VCC_VDD1") (pintype "bidirectional"))
      (node (ref "D47") (pin "VDD") (pinfunction "VCC_VDD") (pintype "bidirectional"))
      (node (ref "D47") (pin "VDD1") (pinfunction "VCC_VDD1") (pintype "bidirectional"))
      (node (ref "D48") (pin "VDD") (pinfunction "VCC_VDD") (pintype "bidirectional"))
      (node (ref "D48") (pin "VDD1") (pinfunction "VCC_VDD1") (pintype "bidirectional"))
      (node (ref "D49") (pin "VDD") (pinfunction "VCC_VDD") (pintype "bidirectional"))
      (node (ref "D49") (pin "VDD1") (pinfunction "VCC_VDD1") (pintype "bidirectional"))
      (node (ref "D5") (pin "VDD") (pinfunction "VCC_VDD") (pintype "bidirectional"))
      (node (ref "D5") (pin "VDD1") (pinfunction "VCC_VDD1") (pintype "bidirectional"))
      (node (ref "D50") (pin "VDD") (pinfunction "VCC_VDD") (pintype "bidirectional"))
      (node (ref "D50") (pin "VDD1") (pinfunction "VCC_VDD1") (pintype "bidirectional"))
      (node (ref "D51") (pin "VDD") (pinfunction "VCC_VDD") (pintype "bidirectional"))
      (node (ref "D51") (pin "VDD1") (pinfunction "VCC_VDD1") (pintype "bidirectional"))
      (node (ref "D52") (pin "VDD") (pinfunction "VCC_VDD") (pintype "bidirectional"))
      (node (ref "D52") (pin "VDD1") (pinfunction "VCC_VDD1") (pintype "bidirectional"))
      (node (ref "D53") (pin "VDD") (pinfunction "VCC_VDD") (pintype "bidirectional"))
      (node (ref "D53") (pin "VDD1") (pinfunction "VCC_VDD1") (pintype "bidirectional"))
      (node (ref "D54") (pin "VDD") (pinfunction "VCC_VDD") (pintype "bidirectional"))
      (node (ref "D54") (pin "VDD1") (pinfunction "VCC_VDD1") (pintype "bidirectional"))
      (node (ref "D55") (pin "VDD") (pinfunction "VCC_VDD") (pintype "bidirectional"))
      (node (ref "D55") (pin "VDD1") (pinfunction "VCC_VDD1") (pintype "bidirectional"))
      (node (ref "D56") (pin "VDD") (pinfunction "VCC_VDD") (pintype "bidirectional"))
      (node (ref "D56") (pin "VDD1") (pinfunction "VCC_VDD1") (pintype "bidirectional"))
      (node (ref "D57") (pin "VDD") (pinfunction "VCC_VDD") (pintype "bidirectional"))
      (node (ref "D57") (pin "VDD1") (pinfunction "VCC_VDD1") (pintype "bidirectional"))
      (node (ref "D58") (pin "VDD") (pinfunction "VCC_VDD") (pintype "bidirectional"))
      (node (ref "D58") (pin "VDD1") (pinfunction "VCC_VDD1") (pintype "bidirectional"))
      (node (ref "D59") (pin "VDD") (pinfunction "VCC_VDD") (pintype "bidirectional"))
      (node (ref "D59") (pin "VDD1") (pinfunction "VCC_VDD1") (pintype "bidirectional"))
      (node (ref "D6") (pin "VDD") (pinfunction "VCC_VDD") (pintype "bidirectional"))
      (node (ref "D6") (pin "VDD1") (pinfunction "VCC_VDD1") (pintype "bidirectional"))
      (node (ref "D60") (pin "VDD") (pinfunction "VCC_VDD") (pintype "bidirectional"))
      (node (ref "D60") (pin "VDD1") (pinfunction "VCC_VDD1") (pintype "bidirectional"))
      (node (ref "D61") (pin "VDD") (pinfunction "VCC_VDD") (pintype "bidirectional"))
      (node (ref "D61") (pin "VDD1") (pinfunction "VCC_VDD1") (pintype "bidirectional"))
      (node (ref "D62") (pin "VDD") (pinfunction "VCC_VDD") (pintype "bidirectional"))
      (node (ref "D62") (pin "VDD1") (pinfunction "VCC_VDD1") (pintype "bidirectional"))
      (node (ref "D63") (pin "VDD") (pinfunction "VCC_VDD") (pintype "bidirectional"))
      (node (ref "D63") (pin "VDD1") (pinfunction "VCC_VDD1") (pintype "bidirectional"))
      (node (ref "D64") (pin "VDD") (pinfunction "VCC_VDD") (pintype "bidirectional"))
      (node (ref "D64") (pin "VDD1") (pinfunction "VCC_VDD1") (pintype "bidirectional"))
      (node (ref "D65") (pin "VDD") (pinfunction "VCC_VDD") (pintype "bidirectional"))
      (node (ref "D65") (pin "VDD1") (pinfunction "VCC_VDD1") (pintype "bidirectional"))
      (node (ref "D7") (pin "VDD") (pinfunction "VCC_VDD") (pintype "bidirectional"))
      (node (ref "D7") (pin "VDD1") (pinfunction "VCC_VDD1") (pintype "bidirectional"))
      (node (ref "D8") (pin "VDD") (pinfunction "VCC_VDD") (pintype "bidirectional"))
      (node (ref "D8") (pin "VDD1") (pinfunction "VCC_VDD1") (pintype "bidirectional"))
      (node (ref "D9") (pin "VDD") (pinfunction "VCC_VDD") (pintype "bidirectional"))
      (node (ref "D9") (pin "VDD1") (pinfunction "VCC_VDD1") (pintype "bidirectional"))
      (node (ref "IC1") (pin "8") (pinfunction "VCC(B)_8") (pintype "bidirectional"))
      (node (ref "PWR_IN") (pin "1") (pinfunction "1_1") (pintype "passive"))
      (node (ref "PWR_OUT") (pin "1") (pinfunction "1_1") (pintype "passive"))
    )
    (net (code "2") (name "CKI") (class "Default")
      (node (ref "IC1") (pin "6") (pinfunction "2B_6") (pintype "bidirectional"))
      (node (ref "R4") (pin "1") (pinfunction "1_1") (pintype "passive"))
      (node (ref "SERIAL_IN") (pin "1") (pinfunction "1_1") (pintype "passive"))
    )
    (net (code "3") (name "CKO") (class "Default")
      (node (ref "D65") (pin "CO") (pinfunction "CO_CO") (pintype "bidirectional"))
      (node (ref "SERIAL_OUT") (pin "1") (pinfunction "1_1") (pintype "passive"))
    )
    (net (code "4") (name "CLK") (class "Default")
      (node (ref "JP2") (pin "1") (pinfunction "1_1") (pintype "passive"))
      (node (ref "JP2") (pin "2") (pinfunction "2_2") (pintype "passive"))
      (node (ref "R3") (pin "2") (pinfunction "2_2") (pintype "passive"))
      (node (ref "U1") (pin "36") (pinfunction "PA14-BOOT0_36") (pintype "bidirectional"))
    )
    (net (code "5") (name "DATA") (class "Default")
      (node (ref "JP2") (pin "3") (pinfunction "3_3") (pintype "passive"))
      (node (ref "U1") (pin "35") (pinfunction "PA13_35") (pintype "bidirectional"))
    )
    (net (code "6") (name "GND") (class "Default")
      (node (ref "C10") (pin "2") (pinfunction "2_2") (pintype "passive"))
      (node (ref "C11") (pin "2") (pinfunction "2_2") (pintype "passive"))
      (node (ref "C12") (pin "2") (pinfunction "2_2") (pintype "passive"))
      (node (ref "C13") (pin "2") (pinfunction "2_2") (pintype "passive"))
      (node (ref "C14") (pin "2") (pinfunction "2_2") (pintype "passive"))
      (node (ref "C15") (pin "2") (pinfunction "2_2") (pintype "passive"))
      (node (ref "C16") (pin "2") (pinfunction "2_2") (pintype "passive"))
      (node (ref "C17") (pin "2") (pinfunction "2_2") (pintype "passive"))
      (node (ref "C18") (pin "2") (pinfunction "2_2") (pintype "passive"))
      (node (ref "C19") (pin "2") (pinfunction "2_2") (pintype "passive"))
      (node (ref "C20") (pin "2") (pinfunction "2_2") (pintype "passive"))
      (node (ref "C21") (pin "2") (pinfunction "2_2") (pintype "passive"))
      (node (ref "C22") (pin "2") (pinfunction "2_2") (pintype "passive"))
      (node (ref "C23") (pin "2") (pinfunction "2_2") (pintype "passive"))
      (node (ref "C24") (pin "2") (pinfunction "2_2") (pintype "passive"))
      (node (ref "C25") (pin "2") (pinfunction "2_2") (pintype "passive"))
      (node (ref "C26") (pin "2") (pinfunction "2_2") (pintype "passive"))
      (node (ref "C27") (pin "2") (pinfunction "2_2") (pintype "passive"))
      (node (ref "C3") (pin "2") (pinfunction "2_2") (pintype "passive"))
      (node (ref "C30") (pin "2") (pinfunction "2_2") (pintype "passive"))
      (node (ref "C31") (pin "2") (pinfunction "2_2") (pintype "passive"))
      (node (ref "C32") (pin "2") (pinfunction "2_2") (pintype "passive"))
      (node (ref "C4") (pin "2") (pinfunction "2_2") (pintype "passive"))
      (node (ref "C8") (pin "2") (pinfunction "2_2") (pintype "passive"))
      (node (ref "C9") (pin "2") (pinfunction "2_2") (pintype "passive"))
      (node (ref "D1") (pin "C") (pinfunction "C_C") (pintype "passive"))
      (node (ref "D10") (pin "GND") (pinfunction "GND_GND") (pintype "bidirectional"))
      (node (ref "D11") (pin "GND") (pinfunction "GND_GND") (pintype "bidirectional"))
      (node (ref "D12") (pin "GND") (pinfunction "GND_GND") (pintype "bidirectional"))
      (node (ref "D13") (pin "GND") (pinfunction "GND_GND") (pintype "bidirectional"))
      (node (ref "D14") (pin "GND") (pinfunction "GND_GND") (pintype "bidirectional"))
      (node (ref "D15") (pin "GND") (pinfunction "GND_GND") (pintype "bidirectional"))
      (node (ref "D16") (pin "GND") (pinfunction "GND_GND") (pintype "bidirectional"))
      (node (ref "D17") (pin "GND") (pinfunction "GND_GND") (pintype "bidirectional"))
      (node (ref "D18") (pin "GND") (pinfunction "GND_GND") (pintype "bidirectional"))
      (node (ref "D19") (pin "GND") (pinfunction "GND_GND") (pintype "bidirectional"))
      (node (ref "D2") (pin "GND") (pinfunction "GND_GND") (pintype "bidirectional"))
      (node (ref "D20") (pin "GND") (pinfunction "GND_GND") (pintype "bidirectional"))
      (node (ref "D21") (pin "GND") (pinfunction "GND_GND") (pintype "bidirectional"))
      (node (ref "D22") (pin "GND") (pinfunction "GND_GND") (pintype "bidirectional"))
      (node (ref "D23") (pin "GND") (pinfunction "GND_GND") (pintype "bidirectional"))
      (node (ref "D24") (pin "GND") (pinfunction "GND_GND") (pintype "bidirectional"))
      (node (ref "D25") (pin "GND") (pinfunction "GND_GND") (pintype "bidirectional"))
      (node (ref "D26") (pin "GND") (pinfunction "GND_GND") (pintype "bidirectional"))
      (node (ref "D27") (pin "GND") (pinfunction "GND_GND") (pintype "bidirectional"))
      (node (ref "D28") (pin "GND") (pinfunction "GND_GND") (pintype "bidirectional"))
      (node (ref "D29") (pin "GND") (pinfunction "GND_GND") (pintype "bidirectional"))
      (node (ref "D3") (pin "GND") (pinfunction "GND_GND") (pintype "bidirectional"))
      (node (ref "D30") (pin "GND") (pinfunction "GND_GND") (pintype "bidirectional"))
      (node (ref "D31") (pin "GND") (pinfunction "GND_GND") (pintype "bidirectional"))
      (node (ref "D32") (pin "GND") (pinfunction "GND_GND") (pintype "bidirectional"))
      (node (ref "D33") (pin "GND") (pinfunction "GND_GND") (pintype "bidirectional"))
      (node (ref "D34") (pin "GND") (pinfunction "GND_GND") (pintype "bidirectional"))
      (node (ref "D35") (pin "GND") (pinfunction "GND_GND") (pintype "bidirectional"))
      (node (ref "D36") (pin "GND") (pinfunction "GND_GND") (pintype "bidirectional"))
      (node (ref "D37") (pin "GND") (pinfunction "GND_GND") (pintype "bidirectional"))
      (node (ref "D38") (pin "GND") (pinfunction "GND_GND") (pintype "bidirectional"))
      (node (ref "D39") (pin "GND") (pinfunction "GND_GND") (pintype "bidirectional"))
      (node (ref "D4") (pin "GND") (pinfunction "GND_GND") (pintype "bidirectional"))
      (node (ref "D40") (pin "GND") (pinfunction "GND_GND") (pintype "bidirectional"))
      (node (ref "D41") (pin "GND") (pinfunction "GND_GND") (pintype "bidirectional"))
      (node (ref "D42") (pin "GND") (pinfunction "GND_GND") (pintype "bidirectional"))
      (node (ref "D43") (pin "GND") (pinfunction "GND_GND") (pintype "bidirectional"))
      (node (ref "D44") (pin "GND") (pinfunction "GND_GND") (pintype "bidirectional"))
      (node (ref "D45") (pin "GND") (pinfunction "GND_GND") (pintype "bidirectional"))
      (node (ref "D46") (pin "GND") (pinfunction "GND_GND") (pintype "bidirectional"))
      (node (ref "D47") (pin "GND") (pinfunction "GND_GND") (pintype "bidirectional"))
      (node (ref "D48") (pin "GND") (pinfunction "GND_GND") (pintype "bidirectional"))
      (node (ref "D49") (pin "GND") (pinfunction "GND_GND") (pintype "bidirectional"))
      (node (ref "D5") (pin "GND") (pinfunction "GND_GND") (pintype "bidirectional"))
      (node (ref "D50") (pin "GND") (pinfunction "GND_GND") (pintype "bidirectional"))
      (node (ref "D51") (pin "GND") (pinfunction "GND_GND") (pintype "bidirectional"))
      (node (ref "D52") (pin "GND") (pinfunction "GND_GND") (pintype "bidirectional"))
      (node (ref "D53") (pin "GND") (pinfunction "GND_GND") (pintype "bidirectional"))
      (node (ref "D54") (pin "GND") (pinfunction "GND_GND") (pintype "bidirectional"))
      (node (ref "D55") (pin "GND") (pinfunction "GND_GND") (pintype "bidirectional"))
      (node (ref "D56") (pin "GND") (pinfunction "GND_GND") (pintype "bidirectional"))
      (node (ref "D57") (pin "GND") (pinfunction "GND_GND") (pintype "bidirectional"))
      (node (ref "D58") (pin "GND") (pinfunction "GND_GND") (pintype "bidirectional"))
      (node (ref "D59") (pin "GND") (pinfunction "GND_GND") (pintype "bidirectional"))
      (node (ref "D6") (pin "GND") (pinfunction "GND_GND") (pintype "bidirectional"))
      (node (ref "D60") (pin "GND") (pinfunction "GND_GND") (pintype "bidirectional"))
      (node (ref "D61") (pin "GND") (pinfunction "GND_GND") (pintype "bidirectional"))
      (node (ref "D62") (pin "GND") (pinfunction "GND_GND") (pintype "bidirectional"))
      (node (ref "D63") (pin "GND") (pinfunction "GND_GND") (pintype "bidirectional"))
      (node (ref "D64") (pin "GND") (pinfunction "GND_GND") (pintype "bidirectional"))
      (node (ref "D65") (pin "GND") (pinfunction "GND_GND") (pintype "bidirectional"))
      (node (ref "D66") (pin "1") (pinfunction "A_1") (pintype "passive"))
      (node (ref "D7") (pin "GND") (pinfunction "GND_GND") (pintype "bidirectional"))
      (node (ref "D8") (pin "GND") (pinfunction "GND_GND") (pintype "bidirectional"))
      (node (ref "D9") (pin "GND") (pinfunction "GND_GND") (pintype "bidirectional"))
      (node (ref "IC1") (pin "4") (pinfunction "GND_4") (pintype "bidirectional"))
      (node (ref "P1") (pin "PAD_PD10") (pinfunction "GND4_PAD_PD10") (pintype "power_in"))
      (node (ref "P1") (pin "PAD_PD11") (pinfunction "GND5_PAD_PD11") (pintype "power_in"))
      (node (ref "P1") (pin "PAD_PD12") (pinfunction "GND6_PAD_PD12") (pintype "power_in"))
      (node (ref "P1") (pin "PAD_PD7") (pinfunction "GND1_PAD_PD7") (pintype "power_in"))
      (node (ref "P1") (pin "PAD_PD8") (pinfunction "GND2_PAD_PD8") (pintype "power_in"))
      (node (ref "P1") (pin "PAD_PD9") (pinfunction "GND3_PAD_PD9") (pintype "power_in"))
      (node (ref "PWR_IN") (pin "2") (pinfunction "2_2") (pintype "passive"))
      (node (ref "PWR_OUT") (pin "2") (pinfunction "2_2") (pintype "passive"))
      (node (ref "R2") (pin "1") (pinfunction "1_1") (pintype "passive"))
      (node (ref "R3") (pin "1") (pinfunction "1_1") (pintype "passive"))
      (node (ref "U1") (pin "30") (pinfunction "VSS_30") (pintype "passive"))
      (node (ref "U1") (pin "49") (pinfunction "EPAD_49") (pintype "passive"))
      (node (ref "X1") (pin "P$2") (pinfunction "2_P$2") (pintype "passive"))
    )
    (net (code "7") (name "L1_CLK") (class "Default")
      (node (ref "D10") (pin "CI") (pinfunction "CI_CI") (pintype "bidirectional"))
      (node (ref "D9") (pin "CO") (pinfunction "CO_CO") (pintype "bidirectional"))
    )
    (net (code "8") (name "L1_DATA") (class "Default")
      (node (ref "D10") (pin "DI") (pinfunction "DI_DI") (pintype "bidirectional"))
      (node (ref "D9") (pin "DO") (pinfunction "DO_DO") (pintype "bidirectional"))
    )
    (net (code "9") (name "L2_CLK") (class "Default")
      (node (ref "D17") (pin "CO") (pinfunction "CO_CO") (pintype "bidirectional"))
      (node (ref "D18") (pin "CI") (pinfunction "CI_CI") (pintype "bidirectional"))
    )
    (net (code "10") (name "L2_DATA") (class "Default")
      (node (ref "D17") (pin "DO") (pinfunction "DO_DO") (pintype "bidirectional"))
      (node (ref "D18") (pin "DI") (pinfunction "DI_DI") (pintype "bidirectional"))
    )
    (net (code "11") (name "L3_CLK") (class "Default")
      (node (ref "D25") (pin "CO") (pinfunction "CO_CO") (pintype "bidirectional"))
      (node (ref "D26") (pin "CI") (pinfunction "CI_CI") (pintype "bidirectional"))
    )
    (net (code "12") (name "L3_DATA") (class "Default")
      (node (ref "D25") (pin "DO") (pinfunction "DO_DO") (pintype "bidirectional"))
      (node (ref "D26") (pin "DI") (pinfunction "DI_DI") (pintype "bidirectional"))
    )
    (net (code "13") (name "L4_CLK") (class "Default")
      (node (ref "D33") (pin "CO") (pinfunction "CO_CO") (pintype "bidirectional"))
      (node (ref "D34") (pin "CI") (pinfunction "CI_CI") (pintype "bidirectional"))
    )
    (net (code "14") (name "L4_DATA") (class "Default")
      (node (ref "D33") (pin "DO") (pinfunction "DO_DO") (pintype "bidirectional"))
      (node (ref "D34") (pin "DI") (pinfunction "DI_DI") (pintype "bidirectional"))
    )
    (net (code "15") (name "L5_CLK") (class "Default")
      (node (ref "D41") (pin "CO") (pinfunction "CO_CO") (pintype "bidirectional"))
      (node (ref "D42") (pin "CI") (pinfunction "CI_CI") (pintype "bidirectional"))
    )
    (net (code "16") (name "L5_DATA") (class "Default")
      (node (ref "D41") (pin "DO") (pinfunction "DO_DO") (pintype "bidirectional"))
      (node (ref "D42") (pin "DI") (pinfunction "DI_DI") (pintype "bidirectional"))
    )
    (net (code "17") (name "L6_CLK") (class "Default")
      (node (ref "D49") (pin "CO") (pinfunction "CO_CO") (pintype "bidirectional"))
      (node (ref "D50") (pin "CI") (pinfunction "CI_CI") (pintype "bidirectional"))
    )
    (net (code "18") (name "L6_DATA") (class "Default")
      (node (ref "D49") (pin "DO") (pinfunction "DO_DO") (pintype "bidirectional"))
      (node (ref "D50") (pin "DI") (pinfunction "DI_DI") (pintype "bidirectional"))
    )
    (net (code "19") (name "L7_CLK") (class "Default")
      (node (ref "D57") (pin "CO") (pinfunction "CO_CO") (pintype "bidirectional"))
      (node (ref "D58") (pin "CI") (pinfunction "CI_CI") (pintype "bidirectional"))
    )
    (net (code "20") (name "L7_DATA") (class "Default")
      (node (ref "D57") (pin "DO") (pinfunction "DO_DO") (pintype "bidirectional"))
      (node (ref "D58") (pin "DI") (pinfunction "DI_DI") (pintype "bidirectional"))
    )
    (net (code "21") (name "Net-(D1-PadA)") (class "Default")
      (node (ref "D1") (pin "A") (pinfunction "A_A") (pintype "passive"))
      (node (ref "R1") (pin "2") (pinfunction "2_2") (pintype "passive"))
    )
    (net (code "22") (name "Net-(D2-PadCI)") (class "Default")
      (node (ref "D2") (pin "CI") (pinfunction "CI_CI") (pintype "bidirectional"))
      (node (ref "R4") (pin "2") (pinfunction "2_2") (pintype "passive"))
    )
    (net (code "23") (name "Net-(D2-PadCO)") (class "Default")
      (node (ref "D2") (pin "CO") (pinfunction "CO_CO") (pintype "bidirectional"))
      (node (ref "D3") (pin "CI") (pinfunction "CI_CI") (pintype "bidirectional"))
    )
    (net (code "24") (name "Net-(D2-PadDI)") (class "Default")
      (node (ref "D2") (pin "DI") (pinfunction "DI_DI") (pintype "bidirectional"))
      (node (ref "R5") (pin "2") (pinfunction "2_2") (pintype "passive"))
    )
    (net (code "25") (name "Net-(D2-PadDO)") (class "Default")
      (node (ref "D2") (pin "DO") (pinfunction "DO_DO") (pintype "bidirectional"))
      (node (ref "D3") (pin "DI") (pinfunction "DI_DI") (pintype "bidirectional"))
    )
    (net (code "26") (name "Net-(D3-PadCO)") (class "Default")
      (node (ref "D3") (pin "CO") (pinfunction "CO_CO") (pintype "bidirectional"))
      (node (ref "D4") (pin "CI") (pinfunction "CI_CI") (pintype "bidirectional"))
    )
    (net (code "27") (name "Net-(D3-PadDO)") (class "Default")
      (node (ref "D3") (pin "DO") (pinfunction "DO_DO") (pintype "bidirectional"))
      (node (ref "D4") (pin "DI") (pinfunction "DI_DI") (pintype "bidirectional"))
    )
    (net (code "28") (name "Net-(D4-PadCO)") (class "Default")
      (node (ref "D4") (pin "CO") (pinfunction "CO_CO") (pintype "bidirectional"))
      (node (ref "D5") (pin "CI") (pinfunction "CI_CI") (pintype "bidirectional"))
    )
    (net (code "29") (name "Net-(D4-PadDO)") (class "Default")
      (node (ref "D4") (pin "DO") (pinfunction "DO_DO") (pintype "bidirectional"))
      (node (ref "D5") (pin "DI") (pinfunction "DI_DI") (pintype "bidirectional"))
    )
    (net (code "30") (name "Net-(D5-PadCO)") (class "Default")
      (node (ref "D5") (pin "CO") (pinfunction "CO_CO") (pintype "bidirectional"))
      (node (ref "D6") (pin "CI") (pinfunction "CI_CI") (pintype "bidirectional"))
    )
    (net (code "31") (name "Net-(D5-PadDO)") (class "Default")
      (node (ref "D5") (pin "DO") (pinfunction "DO_DO") (pintype "bidirectional"))
      (node (ref "D6") (pin "DI") (pinfunction "DI_DI") (pintype "bidirectional"))
    )
    (net (code "32") (name "Net-(D6-PadCO)") (class "Default")
      (node (ref "D6") (pin "CO") (pinfunction "CO_CO") (pintype "bidirectional"))
      (node (ref "D7") (pin "CI") (pinfunction "CI_CI") (pintype "bidirectional"))
    )
    (net (code "33") (name "Net-(D6-PadDO)") (class "Default")
      (node (ref "D6") (pin "DO") (pinfunction "DO_DO") (pintype "bidirectional"))
      (node (ref "D7") (pin "DI") (pinfunction "DI_DI") (pintype "bidirectional"))
    )
    (net (code "34") (name "Net-(D7-PadCO)") (class "Default")
      (node (ref "D7") (pin "CO") (pinfunction "CO_CO") (pintype "bidirectional"))
      (node (ref "D8") (pin "CI") (pinfunction "CI_CI") (pintype "bidirectional"))
    )
    (net (code "35") (name "Net-(D7-PadDO)") (class "Default")
      (node (ref "D7") (pin "DO") (pinfunction "DO_DO") (pintype "bidirectional"))
      (node (ref "D8") (pin "DI") (pinfunction "DI_DI") (pintype "bidirectional"))
    )
    (net (code "36") (name "Net-(D8-PadCO)") (class "Default")
      (node (ref "D8") (pin "CO") (pinfunction "CO_CO") (pintype "bidirectional"))
      (node (ref "D9") (pin "CI") (pinfunction "CI_CI") (pintype "bidirectional"))
    )
    (net (code "37") (name "Net-(D8-PadDO)") (class "Default")
      (node (ref "D8") (pin "DO") (pinfunction "DO_DO") (pintype "bidirectional"))
      (node (ref "D9") (pin "DI") (pinfunction "DI_DI") (pintype "bidirectional"))
    )
    (net (code "38") (name "Net-(D10-PadCO)") (class "Default")
      (node (ref "D10") (pin "CO") (pinfunction "CO_CO") (pintype "bidirectional"))
      (node (ref "D11") (pin "CI") (pinfunction "CI_CI") (pintype "bidirectional"))
    )
    (net (code "39") (name "Net-(D10-PadDO)") (class "Default")
      (node (ref "D10") (pin "DO") (pinfunction "DO_DO") (pintype "bidirectional"))
      (node (ref "D11") (pin "DI") (pinfunction "DI_DI") (pintype "bidirectional"))
    )
    (net (code "40") (name "Net-(D11-PadCO)") (class "Default")
      (node (ref "D11") (pin "CO") (pinfunction "CO_CO") (pintype "bidirectional"))
      (node (ref "D12") (pin "CI") (pinfunction "CI_CI") (pintype "bidirectional"))
    )
    (net (code "41") (name "Net-(D11-PadDO)") (class "Default")
      (node (ref "D11") (pin "DO") (pinfunction "DO_DO") (pintype "bidirectional"))
      (node (ref "D12") (pin "DI") (pinfunction "DI_DI") (pintype "bidirectional"))
    )
    (net (code "42") (name "Net-(D12-PadCO)") (class "Default")
      (node (ref "D12") (pin "CO") (pinfunction "CO_CO") (pintype "bidirectional"))
      (node (ref "D13") (pin "CI") (pinfunction "CI_CI") (pintype "bidirectional"))
    )
    (net (code "43") (name "Net-(D12-PadDO)") (class "Default")
      (node (ref "D12") (pin "DO") (pinfunction "DO_DO") (pintype "bidirectional"))
      (node (ref "D13") (pin "DI") (pinfunction "DI_DI") (pintype "bidirectional"))
    )
    (net (code "44") (name "Net-(D13-PadCO)") (class "Default")
      (node (ref "D13") (pin "CO") (pinfunction "CO_CO") (pintype "bidirectional"))
      (node (ref "D14") (pin "CI") (pinfunction "CI_CI") (pintype "bidirectional"))
    )
    (net (code "45") (name "Net-(D13-PadDO)") (class "Default")
      (node (ref "D13") (pin "DO") (pinfunction "DO_DO") (pintype "bidirectional"))
      (node (ref "D14") (pin "DI") (pinfunction "DI_DI") (pintype "bidirectional"))
    )
    (net (code "46") (name "Net-(D14-PadCO)") (class "Default")
      (node (ref "D14") (pin "CO") (pinfunction "CO_CO") (pintype "bidirectional"))
      (node (ref "D15") (pin "CI") (pinfunction "CI_CI") (pintype "bidirectional"))
    )
    (net (code "47") (name "Net-(D14-PadDO)") (class "Default")
      (node (ref "D14") (pin "DO") (pinfunction "DO_DO") (pintype "bidirectional"))
      (node (ref "D15") (pin "DI") (pinfunction "DI_DI") (pintype "bidirectional"))
    )
    (net (code "48") (name "Net-(D15-PadCO)") (class "Default")
      (node (ref "D15") (pin "CO") (pinfunction "CO_CO") (pintype "bidirectional"))
      (node (ref "D16") (pin "CI") (pinfunction "CI_CI") (pintype "bidirectional"))
    )
    (net (code "49") (name "Net-(D15-PadDO)") (class "Default")
      (node (ref "D15") (pin "DO") (pinfunction "DO_DO") (pintype "bidirectional"))
      (node (ref "D16") (pin "DI") (pinfunction "DI_DI") (pintype "bidirectional"))
    )
    (net (code "50") (name "Net-(D16-PadCO)") (class "Default")
      (node (ref "D16") (pin "CO") (pinfunction "CO_CO") (pintype "bidirectional"))
      (node (ref "D17") (pin "CI") (pinfunction "CI_CI") (pintype "bidirectional"))
    )
    (net (code "51") (name "Net-(D16-PadDO)") (class "Default")
      (node (ref "D16") (pin "DO") (pinfunction "DO_DO") (pintype "bidirectional"))
      (node (ref "D17") (pin "DI") (pinfunction "DI_DI") (pintype "bidirectional"))
    )
    (net (code "52") (name "Net-(D18-PadCO)") (class "Default")
      (node (ref "D18") (pin "CO") (pinfunction "CO_CO") (pintype "bidirectional"))
      (node (ref "D19") (pin "CI") (pinfunction "CI_CI") (pintype "bidirectional"))
    )
    (net (code "53") (name "Net-(D18-PadDO)") (class "Default")
      (node (ref "D18") (pin "DO") (pinfunction "DO_DO") (pintype "bidirectional"))
      (node (ref "D19") (pin "DI") (pinfunction "DI_DI") (pintype "bidirectional"))
    )
    (net (code "54") (name "Net-(D19-PadCO)") (class "Default")
      (node (ref "D19") (pin "CO") (pinfunction "CO_CO") (pintype "bidirectional"))
      (node (ref "D20") (pin "CI") (pinfunction "CI_CI") (pintype "bidirectional"))
    )
    (net (code "55") (name "Net-(D19-PadDO)") (class "Default")
      (node (ref "D19") (pin "DO") (pinfunction "DO_DO") (pintype "bidirectional"))
      (node (ref "D20") (pin "DI") (pinfunction "DI_DI") (pintype "bidirectional"))
    )
    (net (code "56") (name "Net-(D20-PadCO)") (class "Default")
      (node (ref "D20") (pin "CO") (pinfunction "CO_CO") (pintype "bidirectional"))
      (node (ref "D21") (pin "CI") (pinfunction "CI_CI") (pintype "bidirectional"))
    )
    (net (code "57") (name "Net-(D20-PadDO)") (class "Default")
      (node (ref "D20") (pin "DO") (pinfunction "DO_DO") (pintype "bidirectional"))
      (node (ref "D21") (pin "DI") (pinfunction "DI_DI") (pintype "bidirectional"))
    )
    (net (code "58") (name "Net-(D21-PadCO)") (class "Default")
      (node (ref "D21") (pin "CO") (pinfunction "CO_CO") (pintype "bidirectional"))
      (node (ref "D22") (pin "CI") (pinfunction "CI_CI") (pintype "bidirectional"))
    )
    (net (code "59") (name "Net-(D21-PadDO)") (class "Default")
      (node (ref "D21") (pin "DO") (pinfunction "DO_DO") (pintype "bidirectional"))
      (node (ref "D22") (pin "DI") (pinfunction "DI_DI") (pintype "bidirectional"))
    )
    (net (code "60") (name "Net-(D22-PadCO)") (class "Default")
      (node (ref "D22") (pin "CO") (pinfunction "CO_CO") (pintype "bidirectional"))
      (node (ref "D23") (pin "CI") (pinfunction "CI_CI") (pintype "bidirectional"))
    )
    (net (code "61") (name "Net-(D22-PadDO)") (class "Default")
      (node (ref "D22") (pin "DO") (pinfunction "DO_DO") (pintype "bidirectional"))
      (node (ref "D23") (pin "DI") (pinfunction "DI_DI") (pintype "bidirectional"))
    )
    (net (code "62") (name "Net-(D23-PadCO)") (class "Default")
      (node (ref "D23") (pin "CO") (pinfunction "CO_CO") (pintype "bidirectional"))
      (node (ref "D24") (pin "CI") (pinfunction "CI_CI") (pintype "bidirectional"))
    )
    (net (code "63") (name "Net-(D23-PadDO)") (class "Default")
      (node (ref "D23") (pin "DO") (pinfunction "DO_DO") (pintype "bidirectional"))
      (node (ref "D24") (pin "DI") (pinfunction "DI_DI") (pintype "bidirectional"))
    )
    (net (code "64") (name "Net-(D24-PadCO)") (class "Default")
      (node (ref "D24") (pin "CO") (pinfunction "CO_CO") (pintype "bidirectional"))
      (node (ref "D25") (pin "CI") (pinfunction "CI_CI") (pintype "bidirectional"))
    )
    (net (code "65") (name "Net-(D24-PadDO)") (class "Default")
      (node (ref "D24") (pin "DO") (pinfunction "DO_DO") (pintype "bidirectional"))
      (node (ref "D25") (pin "DI") (pinfunction "DI_DI") (pintype "bidirectional"))
    )
    (net (code "66") (name "Net-(D26-PadCO)") (class "Default")
      (node (ref "D26") (pin "CO") (pinfunction "CO_CO") (pintype "bidirectional"))
      (node (ref "D27") (pin "CI") (pinfunction "CI_CI") (pintype "bidirectional"))
    )
    (net (code "67") (name "Net-(D26-PadDO)") (class "Default")
      (node (ref "D26") (pin "DO") (pinfunction "DO_DO") (pintype "bidirectional"))
      (node (ref "D27") (pin "DI") (pinfunction "DI_DI") (pintype "bidirectional"))
    )
    (net (code "68") (name "Net-(D27-PadCO)") (class "Default")
      (node (ref "D27") (pin "CO") (pinfunction "CO_CO") (pintype "bidirectional"))
      (node (ref "D28") (pin "CI") (pinfunction "CI_CI") (pintype "bidirectional"))
    )
    (net (code "69") (name "Net-(D27-PadDO)") (class "Default")
      (node (ref "D27") (pin "DO") (pinfunction "DO_DO") (pintype "bidirectional"))
      (node (ref "D28") (pin "DI") (pinfunction "DI_DI") (pintype "bidirectional"))
    )
    (net (code "70") (name "Net-(D28-PadCO)") (class "Default")
      (node (ref "D28") (pin "CO") (pinfunction "CO_CO") (pintype "bidirectional"))
      (node (ref "D29") (pin "CI") (pinfunction "CI_CI") (pintype "bidirectional"))
    )
    (net (code "71") (name "Net-(D28-PadDO)") (class "Default")
      (node (ref "D28") (pin "DO") (pinfunction "DO_DO") (pintype "bidirectional"))
      (node (ref "D29") (pin "DI") (pinfunction "DI_DI") (pintype "bidirectional"))
    )
    (net (code "72") (name "Net-(D29-PadCO)") (class "Default")
      (node (ref "D29") (pin "CO") (pinfunction "CO_CO") (pintype "bidirectional"))
      (node (ref "D30") (pin "CI") (pinfunction "CI_CI") (pintype "bidirectional"))
    )
    (net (code "73") (name "Net-(D29-PadDO)") (class "Default")
      (node (ref "D29") (pin "DO") (pinfunction "DO_DO") (pintype "bidirectional"))
      (node (ref "D30") (pin "DI") (pinfunction "DI_DI") (pintype "bidirectional"))
    )
    (net (code "74") (name "Net-(D30-PadCO)") (class "Default")
      (node (ref "D30") (pin "CO") (pinfunction "CO_CO") (pintype "bidirectional"))
      (node (ref "D31") (pin "CI") (pinfunction "CI_CI") (pintype "bidirectional"))
    )
    (net (code "75") (name "Net-(D30-PadDO)") (class "Default")
      (node (ref "D30") (pin "DO") (pinfunction "DO_DO") (pintype "bidirectional"))
      (node (ref "D31") (pin "DI") (pinfunction "DI_DI") (pintype "bidirectional"))
    )
    (net (code "76") (name "Net-(D31-PadCO)") (class "Default")
      (node (ref "D31") (pin "CO") (pinfunction "CO_CO") (pintype "bidirectional"))
      (node (ref "D32") (pin "CI") (pinfunction "CI_CI") (pintype "bidirectional"))
    )
    (net (code "77") (name "Net-(D31-PadDO)") (class "Default")
      (node (ref "D31") (pin "DO") (pinfunction "DO_DO") (pintype "bidirectional"))
      (node (ref "D32") (pin "DI") (pinfunction "DI_DI") (pintype "bidirectional"))
    )
    (net (code "78") (name "Net-(D32-PadCO)") (class "Default")
      (node (ref "D32") (pin "CO") (pinfunction "CO_CO") (pintype "bidirectional"))
      (node (ref "D33") (pin "CI") (pinfunction "CI_CI") (pintype "bidirectional"))
    )
    (net (code "79") (name "Net-(D32-PadDO)") (class "Default")
      (node (ref "D32") (pin "DO") (pinfunction "DO_DO") (pintype "bidirectional"))
      (node (ref "D33") (pin "DI") (pinfunction "DI_DI") (pintype "bidirectional"))
    )
    (net (code "80") (name "Net-(D34-PadCO)") (class "Default")
      (node (ref "D34") (pin "CO") (pinfunction "CO_CO") (pintype "bidirectional"))
      (node (ref "D35") (pin "CI") (pinfunction "CI_CI") (pintype "bidirectional"))
    )
    (net (code "81") (name "Net-(D34-PadDO)") (class "Default")
      (node (ref "D34") (pin "DO") (pinfunction "DO_DO") (pintype "bidirectional"))
      (node (ref "D35") (pin "DI") (pinfunction "DI_DI") (pintype "bidirectional"))
    )
    (net (code "82") (name "Net-(D35-PadCO)") (class "Default")
      (node (ref "D35") (pin "CO") (pinfunction "CO_CO") (pintype "bidirectional"))
      (node (ref "D36") (pin "CI") (pinfunction "CI_CI") (pintype "bidirectional"))
    )
    (net (code "83") (name "Net-(D35-PadDO)") (class "Default")
      (node (ref "D35") (pin "DO") (pinfunction "DO_DO") (pintype "bidirectional"))
      (node (ref "D36") (pin "DI") (pinfunction "DI_DI") (pintype "bidirectional"))
    )
    (net (code "84") (name "Net-(D36-PadCO)") (class "Default")
      (node (ref "D36") (pin "CO") (pinfunction "CO_CO") (pintype "bidirectional"))
      (node (ref "D37") (pin "CI") (pinfunction "CI_CI") (pintype "bidirectional"))
    )
    (net (code "85") (name "Net-(D36-PadDO)") (class "Default")
      (node (ref "D36") (pin "DO") (pinfunction "DO_DO") (pintype "bidirectional"))
      (node (ref "D37") (pin "DI") (pinfunction "DI_DI") (pintype "bidirectional"))
    )
    (net (code "86") (name "Net-(D37-PadCO)") (class "Default")
      (node (ref "D37") (pin "CO") (pinfunction "CO_CO") (pintype "bidirectional"))
      (node (ref "D38") (pin "CI") (pinfunction "CI_CI") (pintype "bidirectional"))
    )
    (net (code "87") (name "Net-(D37-PadDO)") (class "Default")
      (node (ref "D37") (pin "DO") (pinfunction "DO_DO") (pintype "bidirectional"))
      (node (ref "D38") (pin "DI") (pinfunction "DI_DI") (pintype "bidirectional"))
    )
    (net (code "88") (name "Net-(D38-PadCO)") (class "Default")
      (node (ref "D38") (pin "CO") (pinfunction "CO_CO") (pintype "bidirectional"))
      (node (ref "D39") (pin "CI") (pinfunction "CI_CI") (pintype "bidirectional"))
    )
    (net (code "89") (name "Net-(D38-PadDO)") (class "Default")
      (node (ref "D38") (pin "DO") (pinfunction "DO_DO") (pintype "bidirectional"))
      (node (ref "D39") (pin "DI") (pinfunction "DI_DI") (pintype "bidirectional"))
    )
    (net (code "90") (name "Net-(D39-PadCO)") (class "Default")
      (node (ref "D39") (pin "CO") (pinfunction "CO_CO") (pintype "bidirectional"))
      (node (ref "D40") (pin "CI") (pinfunction "CI_CI") (pintype "bidirectional"))
    )
    (net (code "91") (name "Net-(D39-PadDO)") (class "Default")
      (node (ref "D39") (pin "DO") (pinfunction "DO_DO") (pintype "bidirectional"))
      (node (ref "D40") (pin "DI") (pinfunction "DI_DI") (pintype "bidirectional"))
    )
    (net (code "92") (name "Net-(D40-PadCO)") (class "Default")
      (node (ref "D40") (pin "CO") (pinfunction "CO_CO") (pintype "bidirectional"))
      (node (ref "D41") (pin "CI") (pinfunction "CI_CI") (pintype "bidirectional"))
    )
    (net (code "93") (name "Net-(D40-PadDO)") (class "Default")
      (node (ref "D40") (pin "DO") (pinfunction "DO_DO") (pintype "bidirectional"))
      (node (ref "D41") (pin "DI") (pinfunction "DI_DI") (pintype "bidirectional"))
    )
    (net (code "94") (name "Net-(D42-PadCO)") (class "Default")
      (node (ref "D42") (pin "CO") (pinfunction "CO_CO") (pintype "bidirectional"))
      (node (ref "D43") (pin "CI") (pinfunction "CI_CI") (pintype "bidirectional"))
    )
    (net (code "95") (name "Net-(D42-PadDO)") (class "Default")
      (node (ref "D42") (pin "DO") (pinfunction "DO_DO") (pintype "bidirectional"))
      (node (ref "D43") (pin "DI") (pinfunction "DI_DI") (pintype "bidirectional"))
    )
    (net (code "96") (name "Net-(D43-PadCO)") (class "Default")
      (node (ref "D43") (pin "CO") (pinfunction "CO_CO") (pintype "bidirectional"))
      (node (ref "D44") (pin "CI") (pinfunction "CI_CI") (pintype "bidirectional"))
    )
    (net (code "97") (name "Net-(D43-PadDO)") (class "Default")
      (node (ref "D43") (pin "DO") (pinfunction "DO_DO") (pintype "bidirectional"))
      (node (ref "D44") (pin "DI") (pinfunction "DI_DI") (pintype "bidirectional"))
    )
    (net (code "98") (name "Net-(D44-PadCO)") (class "Default")
      (node (ref "D44") (pin "CO") (pinfunction "CO_CO") (pintype "bidirectional"))
      (node (ref "D45") (pin "CI") (pinfunction "CI_CI") (pintype "bidirectional"))
    )
    (net (code "99") (name "Net-(D44-PadDO)") (class "Default")
      (node (ref "D44") (pin "DO") (pinfunction "DO_DO") (pintype "bidirectional"))
      (node (ref "D45") (pin "DI") (pinfunction "DI_DI") (pintype "bidirectional"))
    )
    (net (code "100") (name "Net-(D45-PadCO)") (class "Default")
      (node (ref "D45") (pin "CO") (pinfunction "CO_CO") (pintype "bidirectional"))
      (node (ref "D46") (pin "CI") (pinfunction "CI_CI") (pintype "bidirectional"))
    )
    (net (code "101") (name "Net-(D45-PadDO)") (class "Default")
      (node (ref "D45") (pin "DO") (pinfunction "DO_DO") (pintype "bidirectional"))
      (node (ref "D46") (pin "DI") (pinfunction "DI_DI") (pintype "bidirectional"))
    )
    (net (code "102") (name "Net-(D46-PadCO)") (class "Default")
      (node (ref "D46") (pin "CO") (pinfunction "CO_CO") (pintype "bidirectional"))
      (node (ref "D47") (pin "CI") (pinfunction "CI_CI") (pintype "bidirectional"))
    )
    (net (code "103") (name "Net-(D46-PadDO)") (class "Default")
      (node (ref "D46") (pin "DO") (pinfunction "DO_DO") (pintype "bidirectional"))
      (node (ref "D47") (pin "DI") (pinfunction "DI_DI") (pintype "bidirectional"))
    )
    (net (code "104") (name "Net-(D47-PadCO)") (class "Default")
      (node (ref "D47") (pin "CO") (pinfunction "CO_CO") (pintype "bidirectional"))
      (node (ref "D48") (pin "CI") (pinfunction "CI_CI") (pintype "bidirectional"))
    )
    (net (code "105") (name "Net-(D47-PadDO)") (class "Default")
      (node (ref "D47") (pin "DO") (pinfunction "DO_DO") (pintype "bidirectional"))
      (node (ref "D48") (pin "DI") (pinfunction "DI_DI") (pintype "bidirectional"))
    )
    (net (code "106") (name "Net-(D48-PadCO)") (class "Default")
      (node (ref "D48") (pin "CO") (pinfunction "CO_CO") (pintype "bidirectional"))
      (node (ref "D49") (pin "CI") (pinfunction "CI_CI") (pintype "bidirectional"))
    )
    (net (code "107") (name "Net-(D48-PadDO)") (class "Default")
      (node (ref "D48") (pin "DO") (pinfunction "DO_DO") (pintype "bidirectional"))
      (node (ref "D49") (pin "DI") (pinfunction "DI_DI") (pintype "bidirectional"))
    )
    (net (code "108") (name "Net-(D50-PadCO)") (class "Default")
      (node (ref "D50") (pin "CO") (pinfunction "CO_CO") (pintype "bidirectional"))
      (node (ref "D51") (pin "CI") (pinfunction "CI_CI") (pintype "bidirectional"))
    )
    (net (code "109") (name "Net-(D50-PadDO)") (class "Default")
      (node (ref "D50") (pin "DO") (pinfunction "DO_DO") (pintype "bidirectional"))
      (node (ref "D51") (pin "DI") (pinfunction "DI_DI") (pintype "bidirectional"))
    )
    (net (code "110") (name "Net-(D51-PadCO)") (class "Default")
      (node (ref "D51") (pin "CO") (pinfunction "CO_CO") (pintype "bidirectional"))
      (node (ref "D52") (pin "CI") (pinfunction "CI_CI") (pintype "bidirectional"))
    )
    (net (code "111") (name "Net-(D51-PadDO)") (class "Default")
      (node (ref "D51") (pin "DO") (pinfunction "DO_DO") (pintype "bidirectional"))
      (node (ref "D52") (pin "DI") (pinfunction "DI_DI") (pintype "bidirectional"))
    )
    (net (code "112") (name "Net-(D52-PadCO)") (class "Default")
      (node (ref "D52") (pin "CO") (pinfunction "CO_CO") (pintype "bidirectional"))
      (node (ref "D53") (pin "CI") (pinfunction "CI_CI") (pintype "bidirectional"))
    )
    (net (code "113") (name "Net-(D52-PadDO)") (class "Default")
      (node (ref "D52") (pin "DO") (pinfunction "DO_DO") (pintype "bidirectional"))
      (node (ref "D53") (pin "DI") (pinfunction "DI_DI") (pintype "bidirectional"))
    )
    (net (code "114") (name "Net-(D53-PadCO)") (class "Default")
      (node (ref "D53") (pin "CO") (pinfunction "CO_CO") (pintype "bidirectional"))
      (node (ref "D54") (pin "CI") (pinfunction "CI_CI") (pintype "bidirectional"))
    )
    (net (code "115") (name "Net-(D53-PadDO)") (class "Default")
      (node (ref "D53") (pin "DO") (pinfunction "DO_DO") (pintype "bidirectional"))
      (node (ref "D54") (pin "DI") (pinfunction "DI_DI") (pintype "bidirectional"))
    )
    (net (code "116") (name "Net-(D54-PadCO)") (class "Default")
      (node (ref "D54") (pin "CO") (pinfunction "CO_CO") (pintype "bidirectional"))
      (node (ref "D55") (pin "CI") (pinfunction "CI_CI") (pintype "bidirectional"))
    )
    (net (code "117") (name "Net-(D54-PadDO)") (class "Default")
      (node (ref "D54") (pin "DO") (pinfunction "DO_DO") (pintype "bidirectional"))
      (node (ref "D55") (pin "DI") (pinfunction "DI_DI") (pintype "bidirectional"))
    )
    (net (code "118") (name "Net-(D55-PadCO)") (class "Default")
      (node (ref "D55") (pin "CO") (pinfunction "CO_CO") (pintype "bidirectional"))
      (node (ref "D56") (pin "CI") (pinfunction "CI_CI") (pintype "bidirectional"))
    )
    (net (code "119") (name "Net-(D55-PadDO)") (class "Default")
      (node (ref "D55") (pin "DO") (pinfunction "DO_DO") (pintype "bidirectional"))
      (node (ref "D56") (pin "DI") (pinfunction "DI_DI") (pintype "bidirectional"))
    )
    (net (code "120") (name "Net-(D56-PadCO)") (class "Default")
      (node (ref "D56") (pin "CO") (pinfunction "CO_CO") (pintype "bidirectional"))
      (node (ref "D57") (pin "CI") (pinfunction "CI_CI") (pintype "bidirectional"))
    )
    (net (code "121") (name "Net-(D56-PadDO)") (class "Default")
      (node (ref "D56") (pin "DO") (pinfunction "DO_DO") (pintype "bidirectional"))
      (node (ref "D57") (pin "DI") (pinfunction "DI_DI") (pintype "bidirectional"))
    )
    (net (code "122") (name "Net-(D58-PadCO)") (class "Default")
      (node (ref "D58") (pin "CO") (pinfunction "CO_CO") (pintype "bidirectional"))
      (node (ref "D59") (pin "CI") (pinfunction "CI_CI") (pintype "bidirectional"))
    )
    (net (code "123") (name "Net-(D58-PadDO)") (class "Default")
      (node (ref "D58") (pin "DO") (pinfunction "DO_DO") (pintype "bidirectional"))
      (node (ref "D59") (pin "DI") (pinfunction "DI_DI") (pintype "bidirectional"))
    )
    (net (code "124") (name "Net-(D59-PadCO)") (class "Default")
      (node (ref "D59") (pin "CO") (pinfunction "CO_CO") (pintype "bidirectional"))
      (node (ref "D60") (pin "CI") (pinfunction "CI_CI") (pintype "bidirectional"))
    )
    (net (code "125") (name "Net-(D59-PadDO)") (class "Default")
      (node (ref "D59") (pin "DO") (pinfunction "DO_DO") (pintype "bidirectional"))
      (node (ref "D60") (pin "DI") (pinfunction "DI_DI") (pintype "bidirectional"))
    )
    (net (code "126") (name "Net-(D60-PadCO)") (class "Default")
      (node (ref "D60") (pin "CO") (pinfunction "CO_CO") (pintype "bidirectional"))
      (node (ref "D61") (pin "CI") (pinfunction "CI_CI") (pintype "bidirectional"))
    )
    (net (code "127") (name "Net-(D60-PadDO)") (class "Default")
      (node (ref "D60") (pin "DO") (pinfunction "DO_DO") (pintype "bidirectional"))
      (node (ref "D61") (pin "DI") (pinfunction "DI_DI") (pintype "bidirectional"))
    )
    (net (code "128") (name "Net-(D61-PadCO)") (class "Default")
      (node (ref "D61") (pin "CO") (pinfunction "CO_CO") (pintype "bidirectional"))
      (node (ref "D62") (pin "CI") (pinfunction "CI_CI") (pintype "bidirectional"))
    )
    (net (code "129") (name "Net-(D61-PadDO)") (class "Default")
      (node (ref "D61") (pin "DO") (pinfunction "DO_DO") (pintype "bidirectional"))
      (node (ref "D62") (pin "DI") (pinfunction "DI_DI") (pintype "bidirectional"))
    )
    (net (code "130") (name "Net-(D62-PadCO)") (class "Default")
      (node (ref "D62") (pin "CO") (pinfunction "CO_CO") (pintype "bidirectional"))
      (node (ref "D63") (pin "CI") (pinfunction "CI_CI") (pintype "bidirectional"))
    )
    (net (code "131") (name "Net-(D62-PadDO)") (class "Default")
      (node (ref "D62") (pin "DO") (pinfunction "DO_DO") (pintype "bidirectional"))
      (node (ref "D63") (pin "DI") (pinfunction "DI_DI") (pintype "bidirectional"))
    )
    (net (code "132") (name "Net-(D63-PadCO)") (class "Default")
      (node (ref "D63") (pin "CO") (pinfunction "CO_CO") (pintype "bidirectional"))
      (node (ref "D64") (pin "CI") (pinfunction "CI_CI") (pintype "bidirectional"))
    )
    (net (code "133") (name "Net-(D63-PadDO)") (class "Default")
      (node (ref "D63") (pin "DO") (pinfunction "DO_DO") (pintype "bidirectional"))
      (node (ref "D64") (pin "DI") (pinfunction "DI_DI") (pintype "bidirectional"))
    )
    (net (code "134") (name "Net-(D64-PadCO)") (class "Default")
      (node (ref "D64") (pin "CO") (pinfunction "CO_CO") (pintype "bidirectional"))
      (node (ref "D65") (pin "CI") (pinfunction "CI_CI") (pintype "bidirectional"))
    )
    (net (code "135") (name "Net-(D64-PadDO)") (class "Default")
      (node (ref "D64") (pin "DO") (pinfunction "DO_DO") (pintype "bidirectional"))
      (node (ref "D65") (pin "DI") (pinfunction "DI_DI") (pintype "bidirectional"))
    )
    (net (code "136") (name "Net-(U1-PC13)") (class "Default")
      (node (ref "R1") (pin "1") (pinfunction "1_1") (pintype "passive"))
      (node (ref "U1") (pin "1") (pinfunction "PC13_1") (pintype "bidirectional"))
    )
    (net (code "137") (name "Net-(U1-PF0-OSC_IN)") (class "Default")
      (node (ref "U1") (pin "8") (pinfunction "PF0-OSC_IN_8") (pintype "bidirectional"))
      (node (ref "X1") (pin "P$3") (pinfunction "3_P$3") (pintype "passive"))
    )
    (net (code "138") (name "Net-(U1-PF1-OSC_OUT)") (class "Default")
      (node (ref "U1") (pin "9") (pinfunction "PF1-OSC_OUT_9") (pintype "bidirectional"))
      (node (ref "X1") (pin "P$1") (pinfunction "1_P$1") (pintype "passive"))
    )
    (net (code "139") (name "Net-(U1-PF2-NRST)") (class "Default")
      (node (ref "C8") (pin "1") (pinfunction "1_1") (pintype "passive"))
      (node (ref "R") (pin "1") (pinfunction "1_1") (pintype "passive"))
      (node (ref "U1") (pin "10") (pinfunction "PF2-NRST_10") (pintype "bidirectional"))
    )
    (net (code "140") (name "SDI") (class "Default")
      (node (ref "IC1") (pin "7") (pinfunction "1B_7") (pintype "bidirectional"))
      (node (ref "R5") (pin "1") (pinfunction "1_1") (pintype "passive"))
      (node (ref "SERIAL_IN") (pin "2") (pinfunction "2_2") (pintype "passive"))
    )
    (net (code "141") (name "SDO") (class "Default")
      (node (ref "D65") (pin "DO") (pinfunction "DO_DO") (pintype "bidirectional"))
      (node (ref "SERIAL_OUT") (pin "2") (pinfunction "2_2") (pintype "passive"))
    )
    (net (code "142") (name "SPI1_MOSI") (class "Default")
      (node (ref "IC1") (pin "2") (pinfunction "1A_2") (pintype "bidirectional"))
      (node (ref "U1") (pin "44") (pinfunction "PB5_44") (pintype "bidirectional"))
    )
    (net (code "143") (name "SPI1_SCK") (class "Default")
      (node (ref "IC1") (pin "3") (pinfunction "2A_3") (pintype "bidirectional"))
      (node (ref "U1") (pin "42") (pinfunction "PB3_42") (pintype "bidirectional"))
    )
    (net (code "144") (name "USART1_RX") (class "Default")
      (node (ref "P1") (pin "PAD_PD5") (pinfunction "SD5_PAD_PD5") (pintype "bidirectional"))
      (node (ref "U1") (pin "46") (pinfunction "PB7_46") (pintype "bidirectional"))
    )
    (net (code "145") (name "USART1_TX") (class "Default")
      (node (ref "P1") (pin "PAD_PU5") (pinfunction "SU5_PAD_PU5") (pintype "bidirectional"))
      (node (ref "U1") (pin "45") (pinfunction "PB6_45") (pintype "bidirectional"))
    )
    (net (code "146") (name "USART2_RX") (class "Default")
      (node (ref "P1") (pin "PAD_PD2") (pinfunction "SD2_PAD_PD2") (pintype "bidirectional"))
      (node (ref "U1") (pin "14") (pinfunction "PA3_14") (pintype "bidirectional"))
    )
    (net (code "147") (name "USART2_TX") (class "Default")
      (node (ref "P1") (pin "PAD_PU2") (pinfunction "SU2_PAD_PU2") (pintype "bidirectional"))
      (node (ref "U1") (pin "13") (pinfunction "PA2_13") (pintype "bidirectional"))
    )
    (net (code "148") (name "USART3_RX") (class "Default")
      (node (ref "P1") (pin "PAD_PD3") (pinfunction "SD3_PAD_PD3") (pintype "bidirectional"))
      (node (ref "U1") (pin "23") (pinfunction "PB11_23") (pintype "bidirectional"))
    )
    (net (code "149") (name "USART3_TX") (class "Default")
      (node (ref "P1") (pin "PAD_PU3") (pinfunction "SU3_PAD_PU3") (pintype "bidirectional"))
      (node (ref "U1") (pin "22") (pinfunction "PB10_22") (pintype "bidirectional"))
    )
    (net (code "150") (name "USART4_RX") (class "Default")
      (node (ref "P1") (pin "PAD_PD1") (pinfunction "SD1_PAD_PD1") (pintype "bidirectional"))
      (node (ref "U1") (pin "12") (pinfunction "PA1_12") (pintype "bidirectional"))
    )
    (net (code "151") (name "USART4_TX") (class "Default")
      (node (ref "P1") (pin "PAD_PU1") (pinfunction "SU1_PAD_PU1") (pintype "bidirectional"))
      (node (ref "U1") (pin "11") (pinfunction "PA0_11") (pintype "bidirectional"))
    )
    (net (code "152") (name "USART5_RX") (class "Default")
      (node (ref "P1") (pin "PAD_PD4") (pinfunction "SD4_PAD_PD4") (pintype "bidirectional"))
      (node (ref "U1") (pin "40") (pinfunction "PD2_40") (pintype "bidirectional"))
    )
    (net (code "153") (name "USART5_TX") (class "Default")
      (node (ref "P1") (pin "PAD_PU4") (pinfunction "SU4_PAD_PU4") (pintype "bidirectional"))
      (node (ref "U1") (pin "41") (pinfunction "PD3_41") (pintype "bidirectional"))
    )
    (net (code "154") (name "USART6_RX") (class "Default")
      (node (ref "P1") (pin "PAD_PD6") (pinfunction "SD6_PAD_PD6") (pintype "bidirectional"))
      (node (ref "U1") (pin "48") (pinfunction "PB9_48") (pintype "bidirectional"))
    )
    (net (code "155") (name "USART6_TX") (class "Default")
      (node (ref "P1") (pin "PAD_PU6") (pinfunction "SU6_PAD_PU6") (pintype "bidirectional"))
      (node (ref "U1") (pin "47") (pinfunction "PB8_47") (pintype "bidirectional"))
    )
    (net (code "156") (name "VDD") (class "Default")
      (node (ref "C13") (pin "1") (pinfunction "1_1") (pintype "passive"))
      (node (ref "C3") (pin "1") (pinfunction "1_1") (pintype "passive"))
      (node (ref "C4") (pin "1") (pinfunction "1_1") (pintype "passive"))
      (node (ref "D66") (pin "2") (pinfunction "C_2") (pintype "passive"))
      (node (ref "FB1") (pin "2") (pinfunction "2_2") (pintype "passive"))
      (node (ref "IC1") (pin "1") (pinfunction "VCC(A)_1") (pintype "bidirectional"))
      (node (ref "IC1") (pin "5") (pinfunction "DIR_5") (pintype "bidirectional"))
      (node (ref "P1") (pin "PAD_PU10") (pinfunction "VDD4_PAD_PU10") (pintype "power_in"))
      (node (ref "P1") (pin "PAD_PU11") (pinfunction "VDD5_PAD_PU11") (pintype "power_in"))
      (node (ref "P1") (pin "PAD_PU12") (pinfunction "VDD6_PAD_PU12") (pintype "power_in"))
      (node (ref "P1") (pin "PAD_PU7") (pinfunction "VDD1_PAD_PU7") (pintype "power_in"))
      (node (ref "P1") (pin "PAD_PU8") (pinfunction "VDD2_PAD_PU8") (pintype "power_in"))
      (node (ref "P1") (pin "PAD_PU9") (pinfunction "VDD3_PAD_PU9") (pintype "power_in"))
      (node (ref "U1") (pin "31") (pinfunction "VDDIO2_31") (pintype "power_in"))
    )
    (net (code "157") (name "VDDA") (class "Default")
      (node (ref "C2") (pin "1") (pinfunction "1_1") (pintype "passive"))
      (node (ref "C5") (pin "1") (pinfunction "1_1") (pintype "passive"))
      (node (ref "C6") (pin "1") (pinfunction "1_1") (pintype "passive"))
      (node (ref "C7") (pin "1") (pinfunction "1_1") (pintype "passive"))
      (node (ref "FB1") (pin "1") (pinfunction "1_1") (pintype "passive"))
      (node (ref "U1") (pin "4") (pinfunction "VBAT_4") (pintype "power_in"))
      (node (ref "U1") (pin "5") (pinfunction "VREF+_5") (pintype "power_in"))
      (node (ref "U1") (pin "6") (pinfunction "VDD/VDDA_6") (pintype "power_in"))
    )
    (net (code "158") (name "VSSA") (class "Default")
      (node (ref "C2") (pin "2") (pinfunction "2_2") (pintype "passive"))
      (node (ref "C5") (pin "2") (pinfunction "2_2") (pintype "passive"))
      (node (ref "C6") (pin "2") (pinfunction "2_2") (pintype "passive"))
      (node (ref "C7") (pin "2") (pinfunction "2_2") (pintype "passive"))
      (node (ref "R2") (pin "2") (pinfunction "2_2") (pintype "passive"))
      (node (ref "U1") (pin "7") (pinfunction "VSS/VSSA_7") (pintype "passive"))
    )
    (net (code "159") (name "unconnected-(U1-PA4-Pad15)") (class "Default")
      (node (ref "U1") (pin "15") (pinfunction "PA4_15") (pintype "bidirectional"))
    )
    (net (code "160") (name "unconnected-(U1-PA5-Pad16)") (class "Default")
      (node (ref "U1") (pin "16") (pinfunction "PA5_16") (pintype "bidirectional"))
    )
    (net (code "161") (name "unconnected-(U1-PA6-Pad17)") (class "Default")
      (node (ref "U1") (pin "17") (pinfunction "PA6_17") (pintype "bidirectional"))
    )
    (net (code "162") (name "unconnected-(U1-PA7-Pad18)") (class "Default")
      (node (ref "U1") (pin "18") (pinfunction "PA7_18") (pintype "bidirectional"))
    )
    (net (code "163") (name "unconnected-(U1-PA8-Pad28)") (class "Default")
      (node (ref "U1") (pin "28") (pinfunction "PA8_28") (pintype "bidirectional"))
    )
    (net (code "164") (name "unconnected-(U1-PA9-Pad29)") (class "Default")
      (node (ref "U1") (pin "29") (pinfunction "PA9_29") (pintype "bidirectional"))
    )
    (net (code "165") (name "unconnected-(U1-PA10-Pad32)") (class "Default")
      (node (ref "U1") (pin "32") (pinfunction "PA10_32") (pintype "bidirectional"))
    )
    (net (code "166") (name "unconnected-(U1-PA11[PA9]-Pad33)") (class "Default")
      (node (ref "U1") (pin "33") (pinfunction "PA11[PA9]_33") (pintype "bidirectional"))
    )
    (net (code "167") (name "unconnected-(U1-PA12[PA10]-Pad34)") (class "Default")
      (node (ref "U1") (pin "34") (pinfunction "PA12[PA10]_34") (pintype "bidirectional"))
    )
    (net (code "168") (name "unconnected-(U1-PA15-Pad37)") (class "Default")
      (node (ref "U1") (pin "37") (pinfunction "PA15_37") (pintype "bidirectional"))
    )
    (net (code "169") (name "unconnected-(U1-PB0-Pad19)") (class "Default")
      (node (ref "U1") (pin "19") (pinfunction "PB0_19") (pintype "bidirectional"))
    )
    (net (code "170") (name "unconnected-(U1-PB1-Pad20)") (class "Default")
      (node (ref "U1") (pin "20") (pinfunction "PB1_20") (pintype "bidirectional"))
    )
    (net (code "171") (name "unconnected-(U1-PB2-Pad21)") (class "Default")
      (node (ref "U1") (pin "21") (pinfunction "PB2_21") (pintype "bidirectional"))
    )
    (net (code "172") (name "unconnected-(U1-PB4-Pad43)") (class "Default")
      (node (ref "U1") (pin "43") (pinfunction "PB4_43") (pintype "bidirectional"))
    )
    (net (code "173") (name "unconnected-(U1-PB12-Pad24)") (class "Default")
      (node (ref "U1") (pin "24") (pinfunction "PB12_24") (pintype "bidirectional"))
    )
    (net (code "174") (name "unconnected-(U1-PB13-Pad25)") (class "Default")
      (node (ref "U1") (pin "25") (pinfunction "PB13_25") (pintype "bidirectional"))
    )
    (net (code "175") (name "unconnected-(U1-PB14-Pad26)") (class "Default")
      (node (ref "U1") (pin "26") (pinfunction "PB14_26") (pintype "bidirectional"))
    )
    (net (code "176") (name "unconnected-(U1-PB15-Pad27)") (class "Default")
      (node (ref "U1") (pin "27") (pinfunction "PB15_27") (pintype "bidirectional"))
    )
    (net (code "177") (name "unconnected-(U1-PC14-OSC32_IN-Pad2)") (class "Default")
      (node (ref "U1") (pin "2") (pinfunction "PC14-OSC32_IN_2") (pintype "bidirectional"))
    )
    (net (code "178") (name "unconnected-(U1-PC15-OSC32_OUT-Pad3)") (class "Default")
      (node (ref "U1") (pin "3") (pinfunction "PC15-OSC32_OUT_3") (pintype "bidirectional"))
    )
    (net (code "179") (name "unconnected-(U1-PD0-Pad38)") (class "Default")
      (node (ref "U1") (pin "38") (pinfunction "PD0_38") (pintype "bidirectional"))
    )
    (net (code "180") (name "unconnected-(U1-PD1-Pad39)") (class "Default")
      (node (ref "U1") (pin "39") (pinfunction "PD1_39") (pintype "bidirectional"))
    )
  )
)
